# power_supply_module.net
KiCad netlist of a schematic drawn in EAGLE
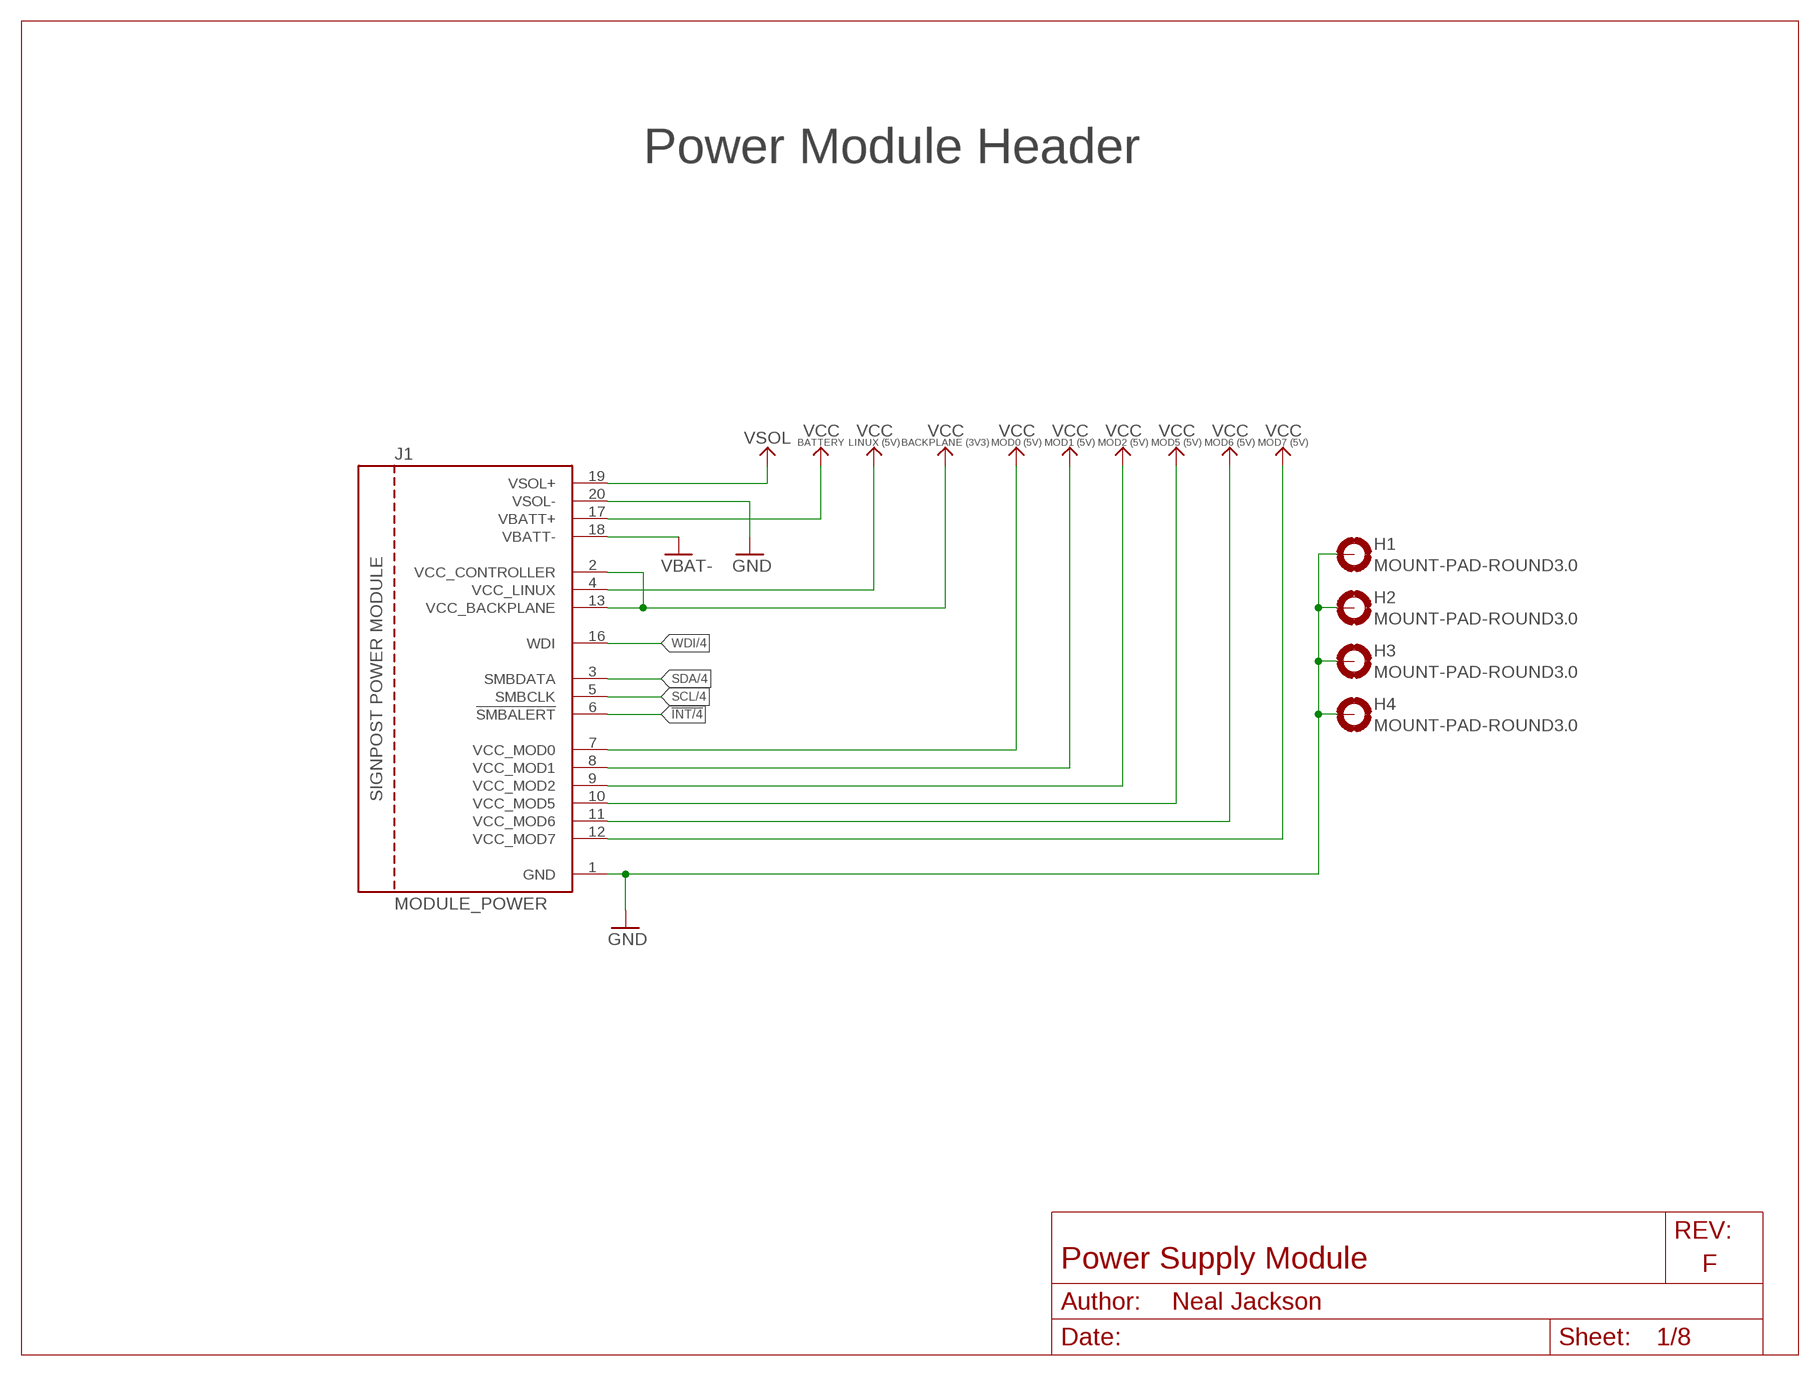
[diagram p0: schematic, sheet 1]
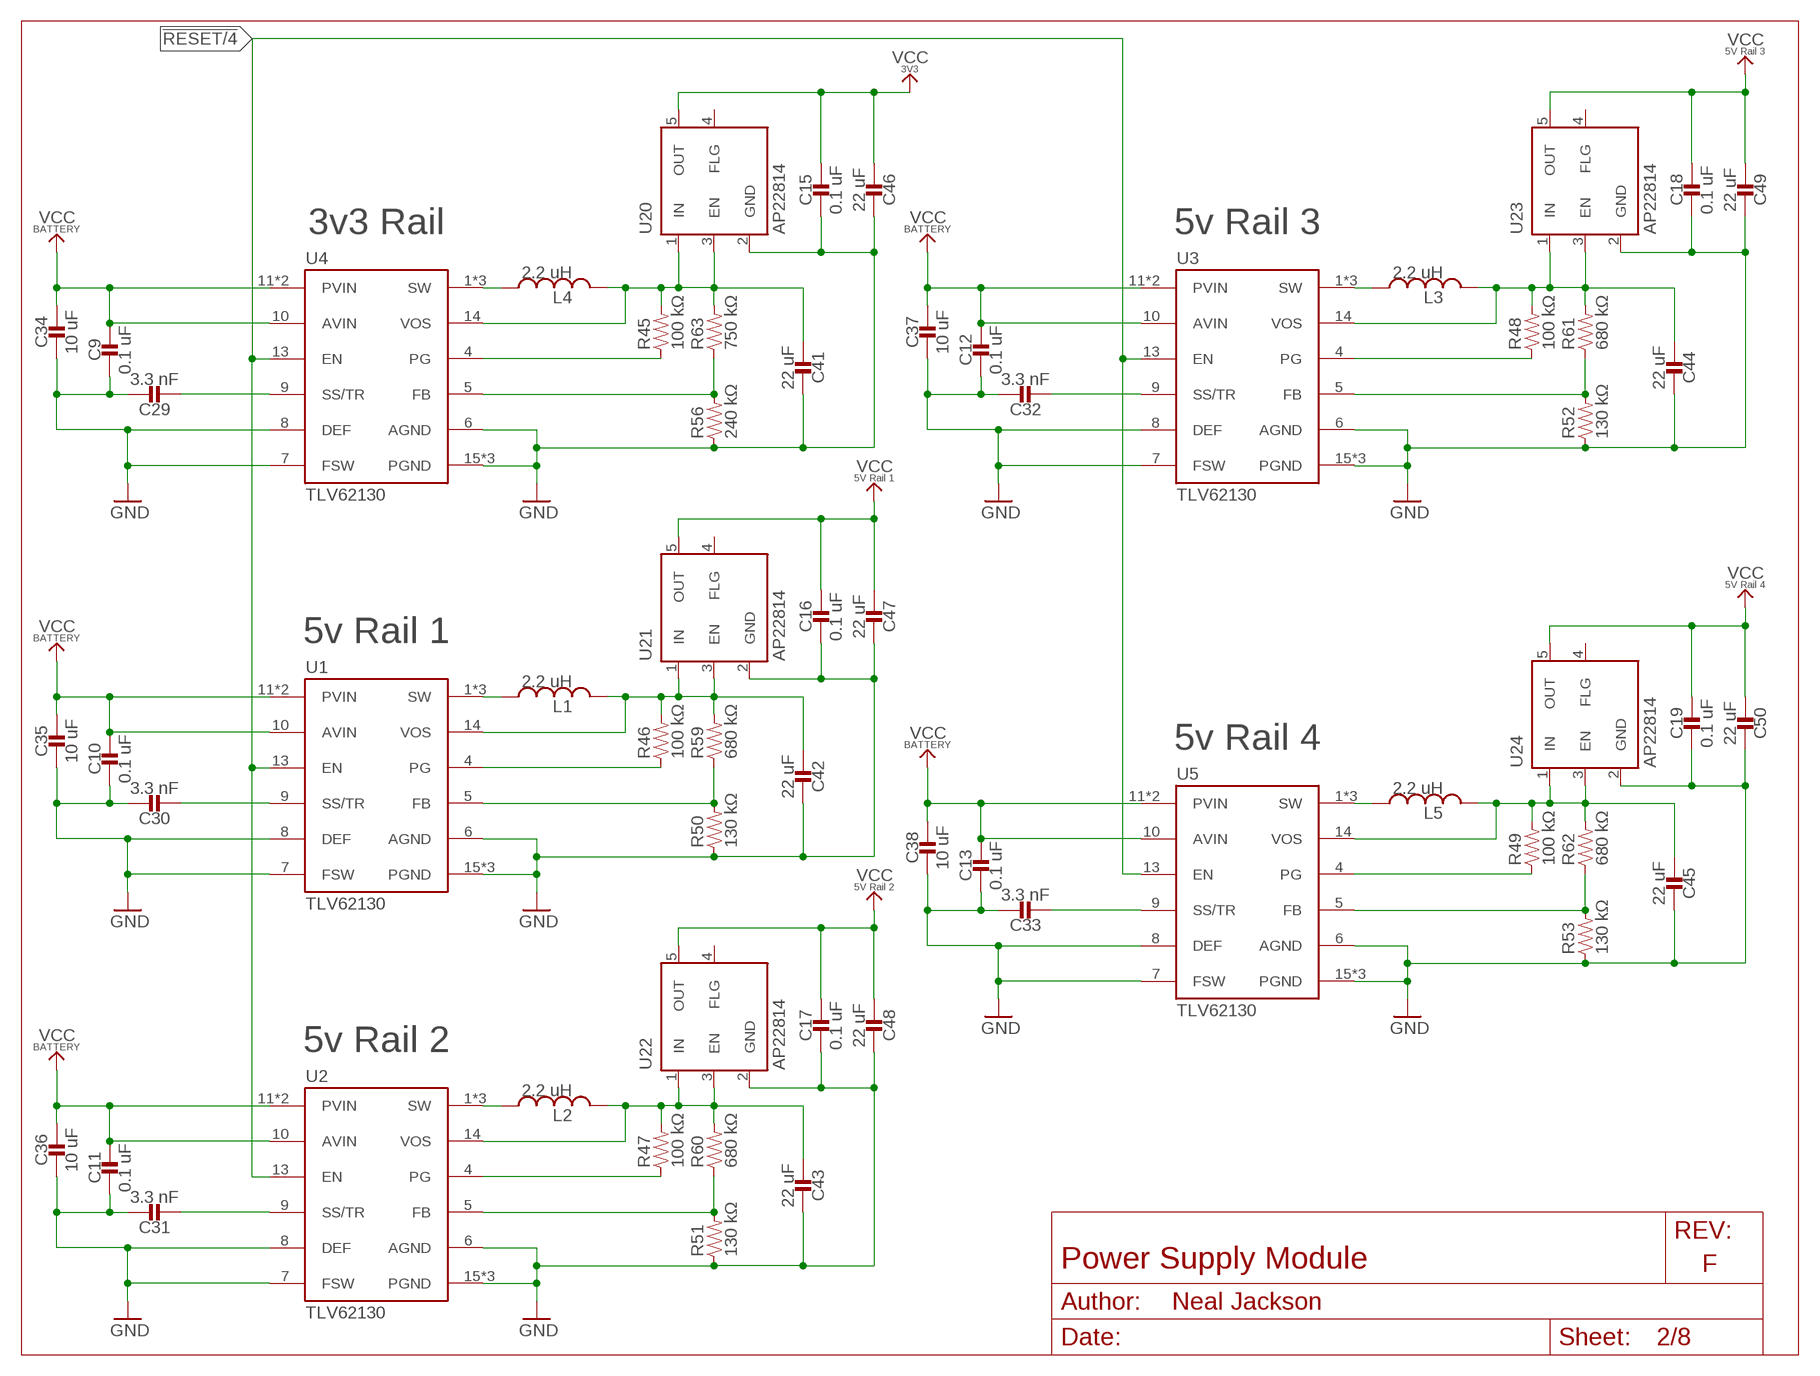
[diagram p1: schematic, sheet 2]
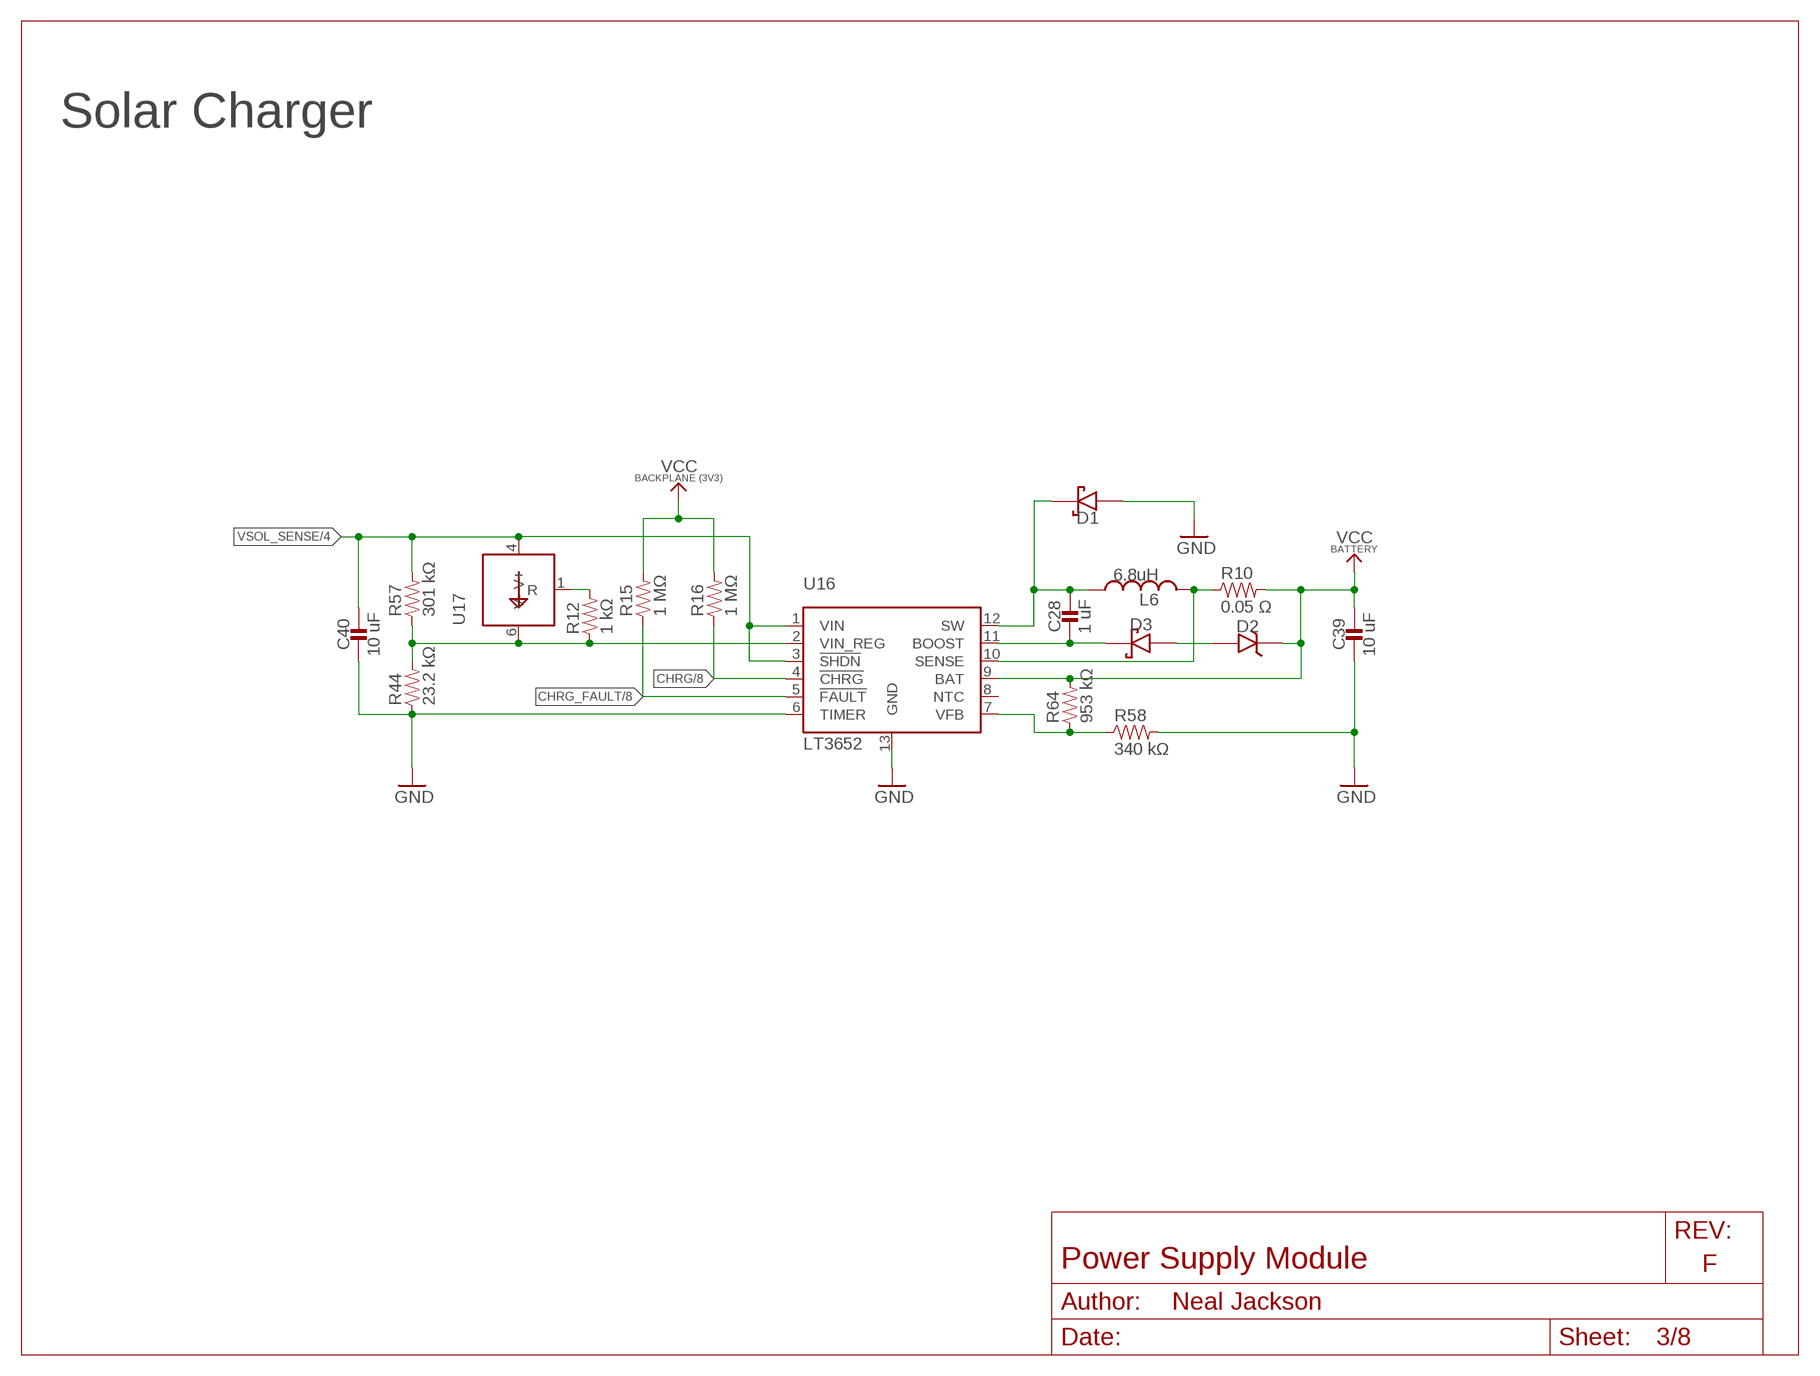
[diagram p2: schematic, sheet 3]
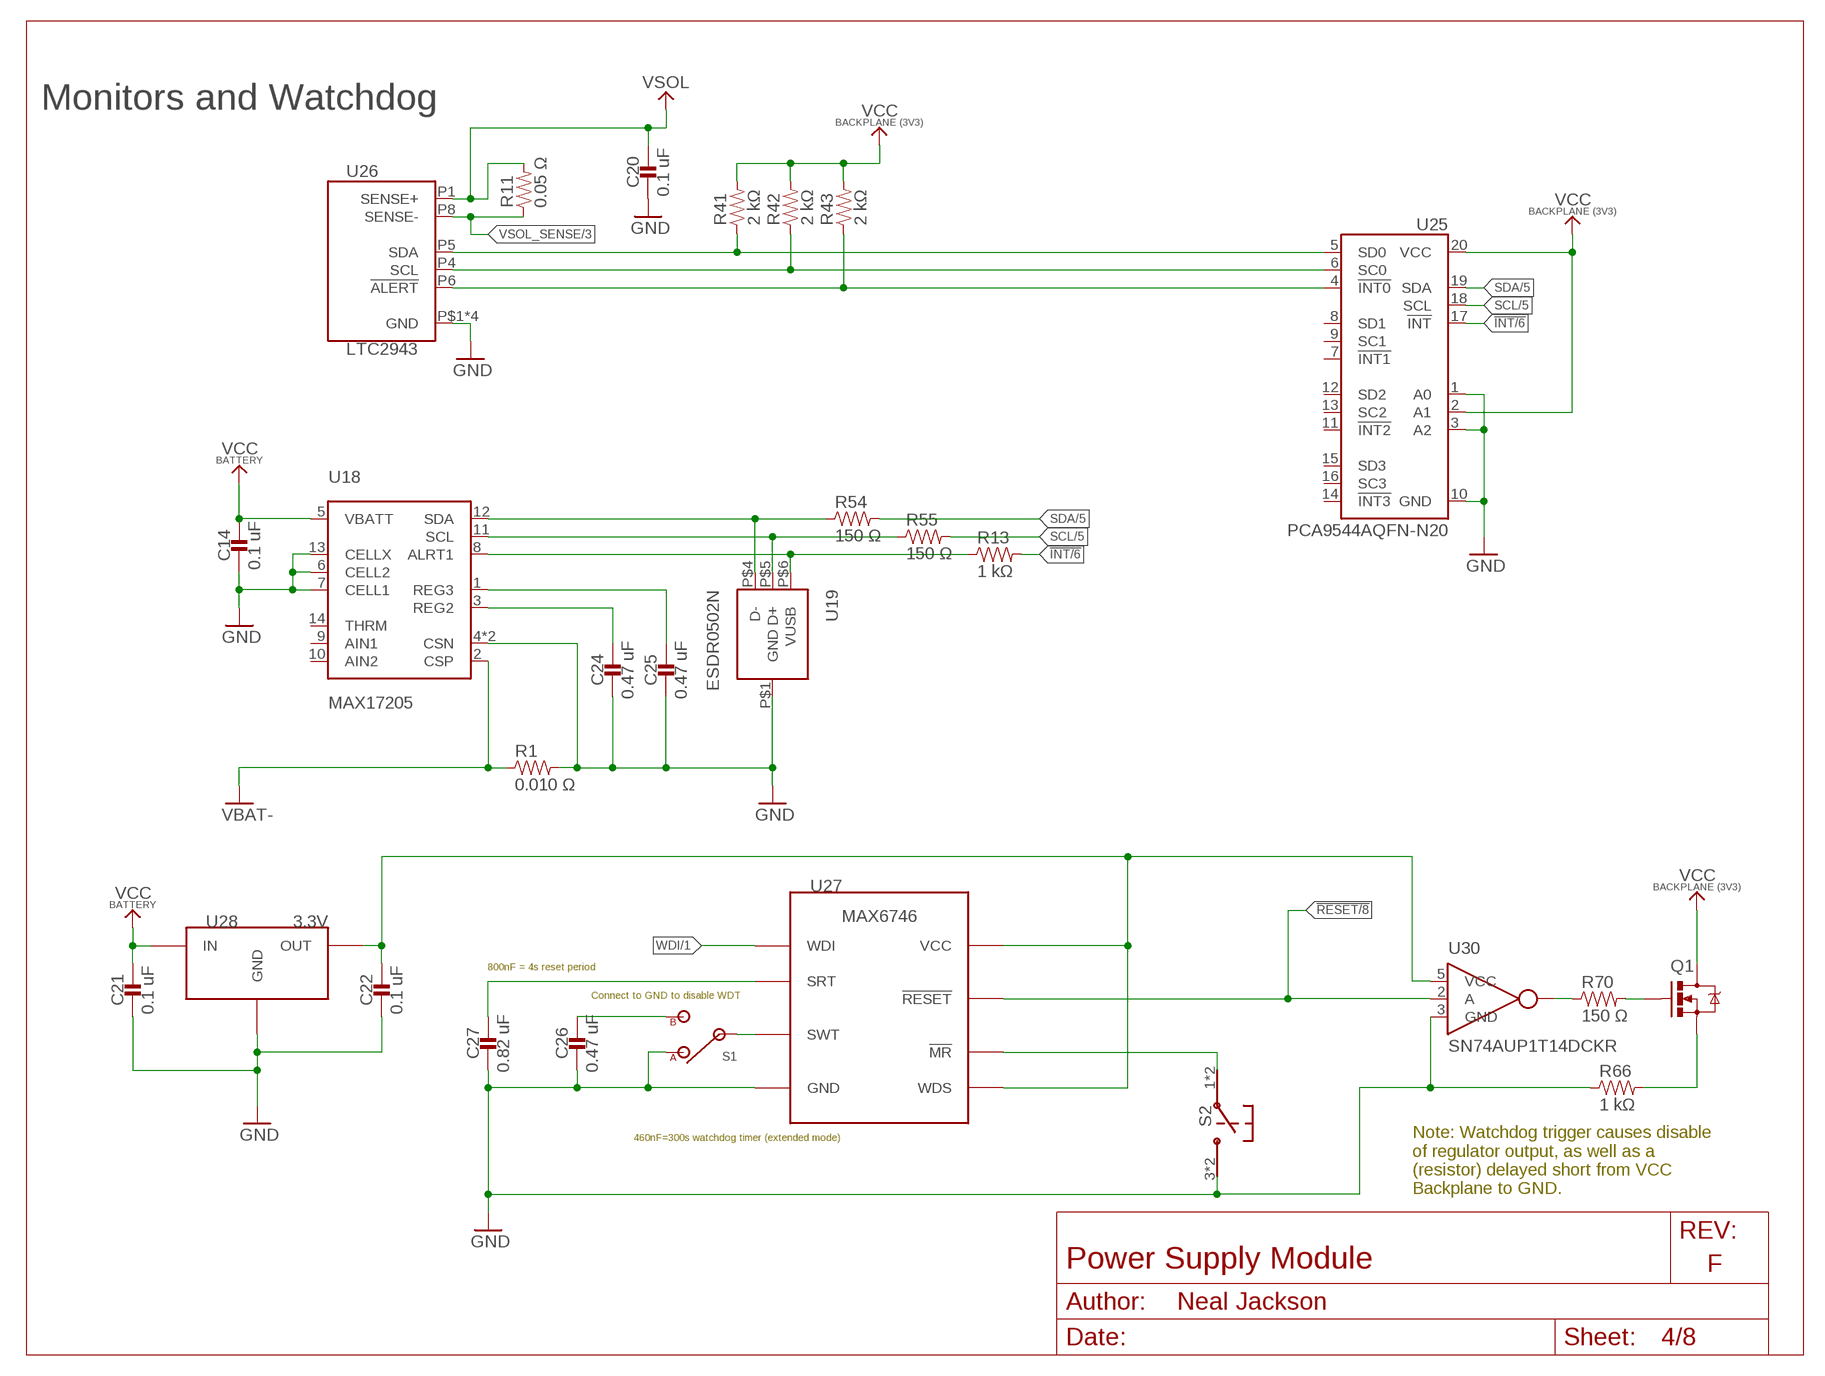
[diagram p3: schematic, sheet 4]
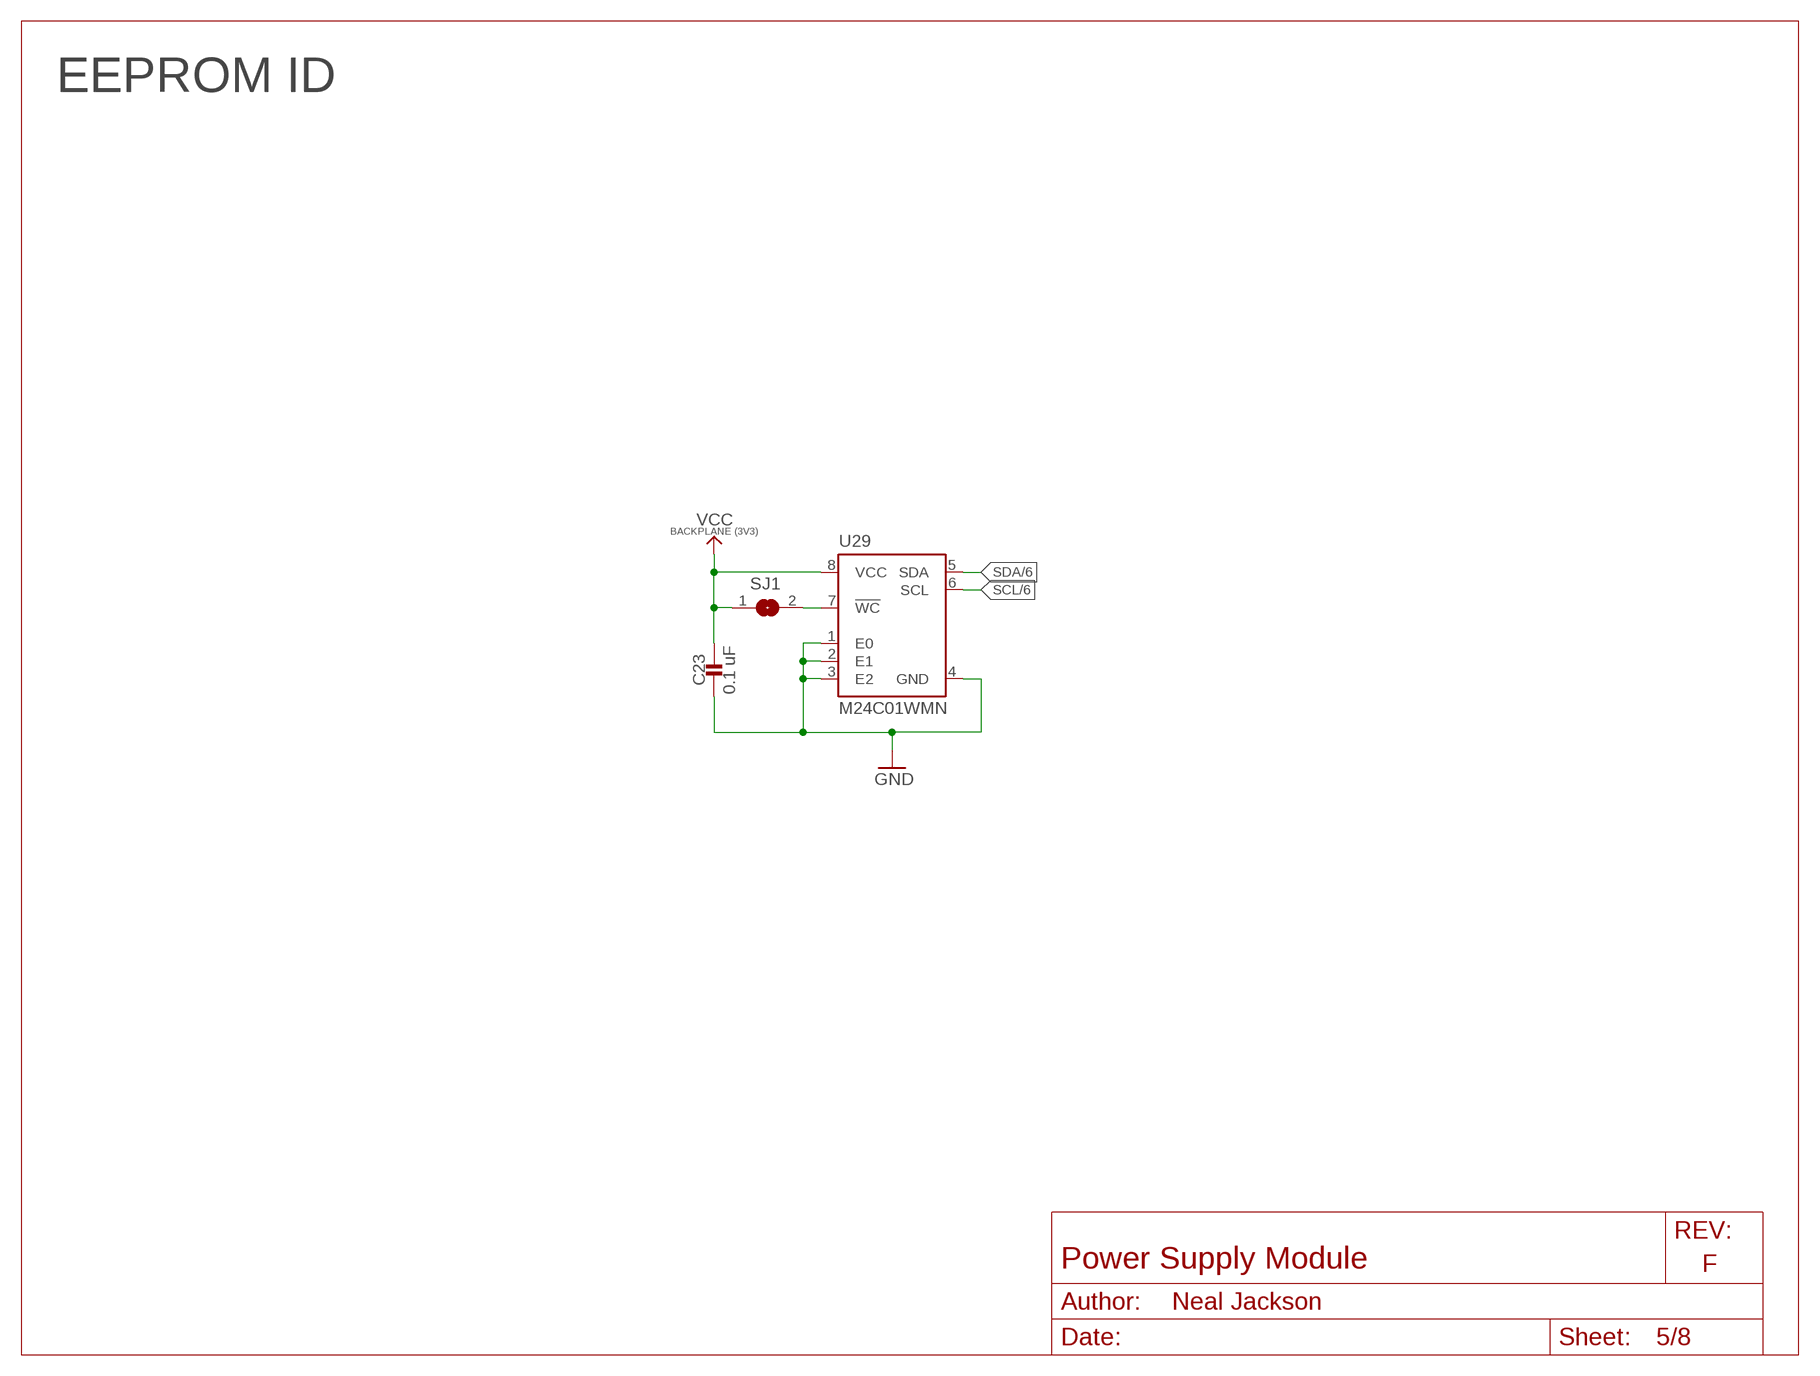
[diagram p4: schematic, sheet 5]
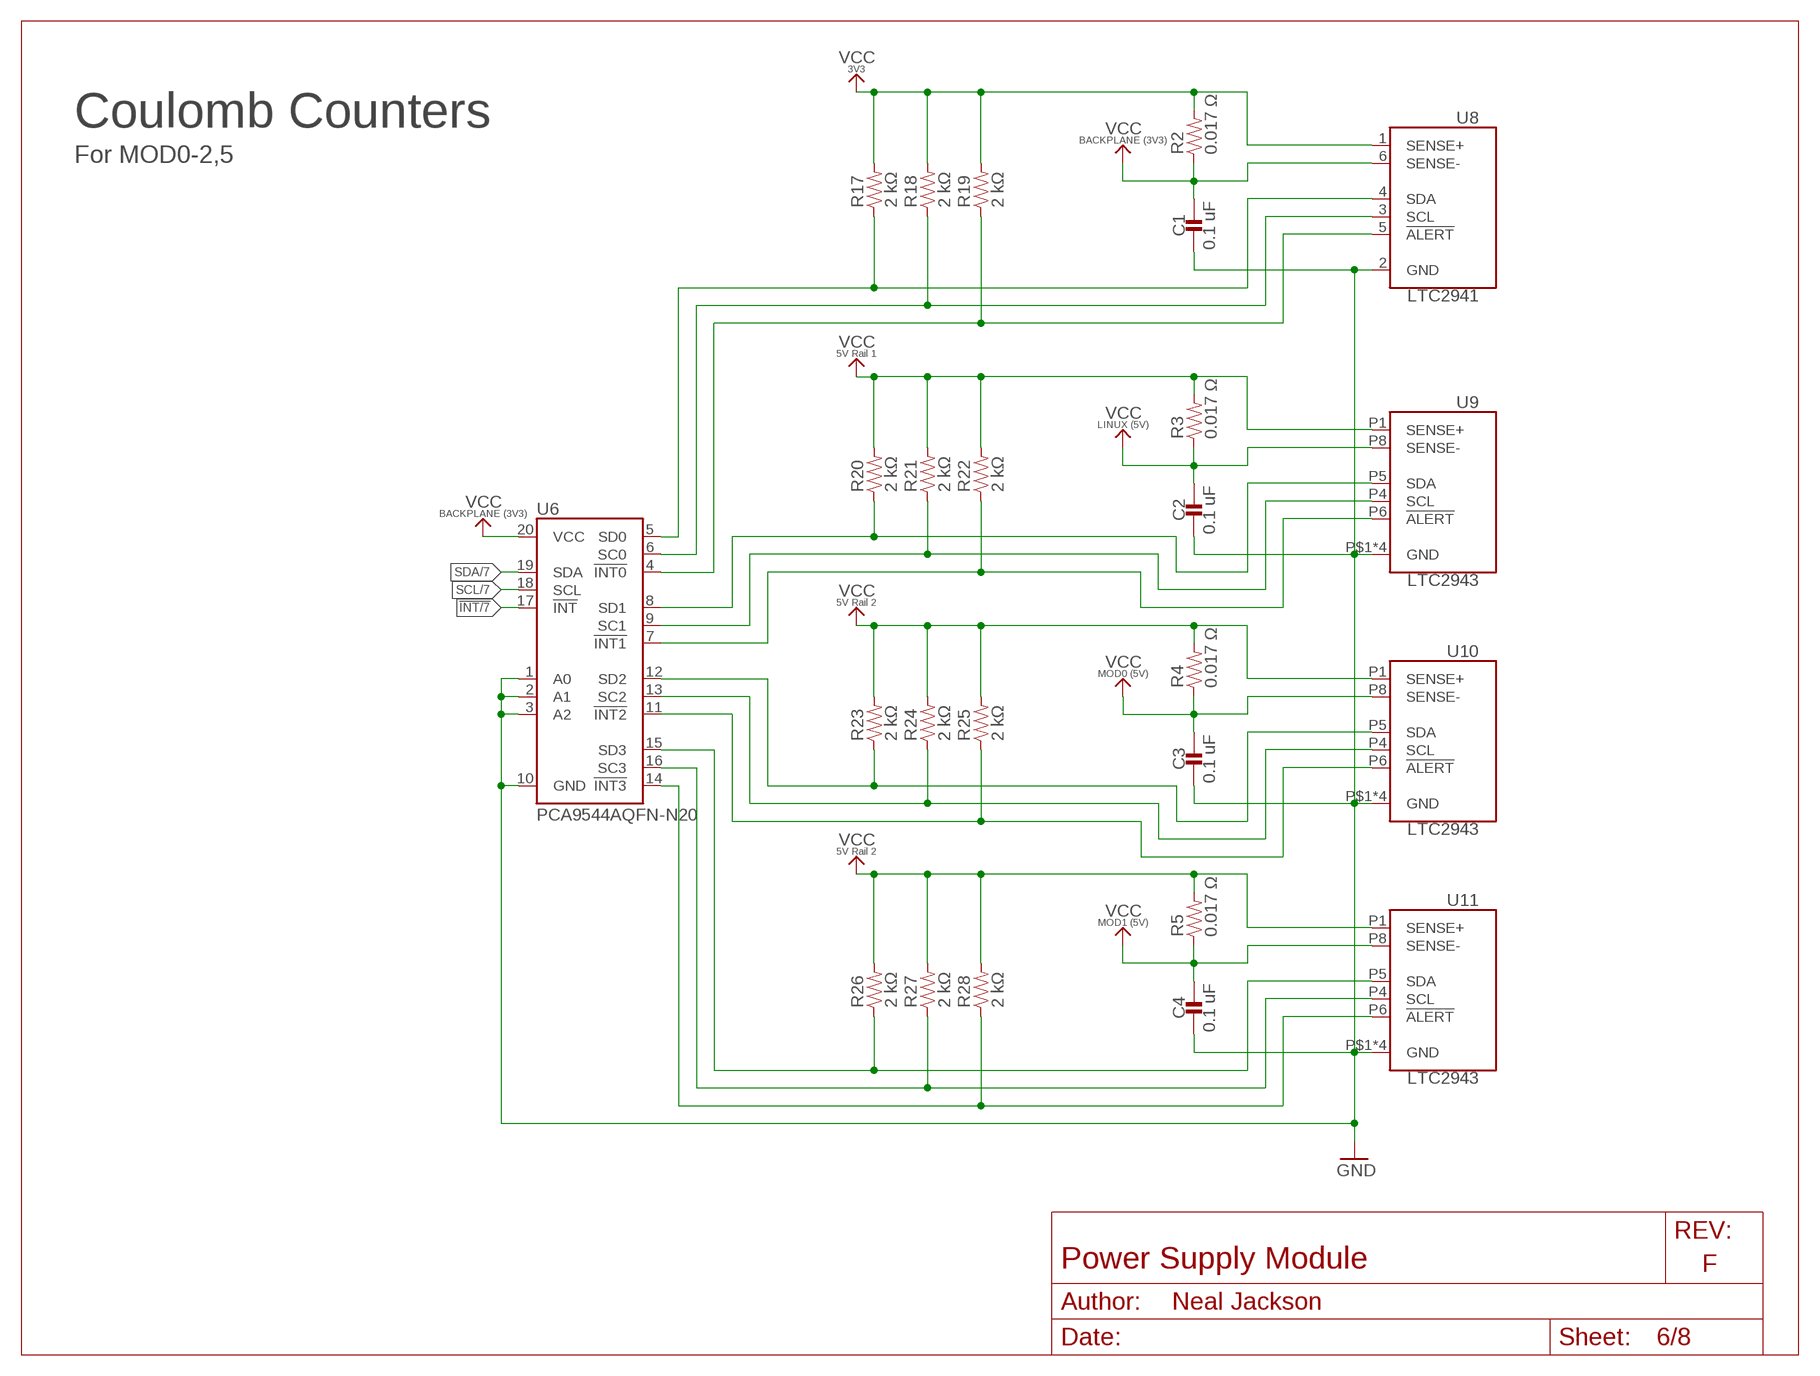
[diagram p5: schematic, sheet 6]
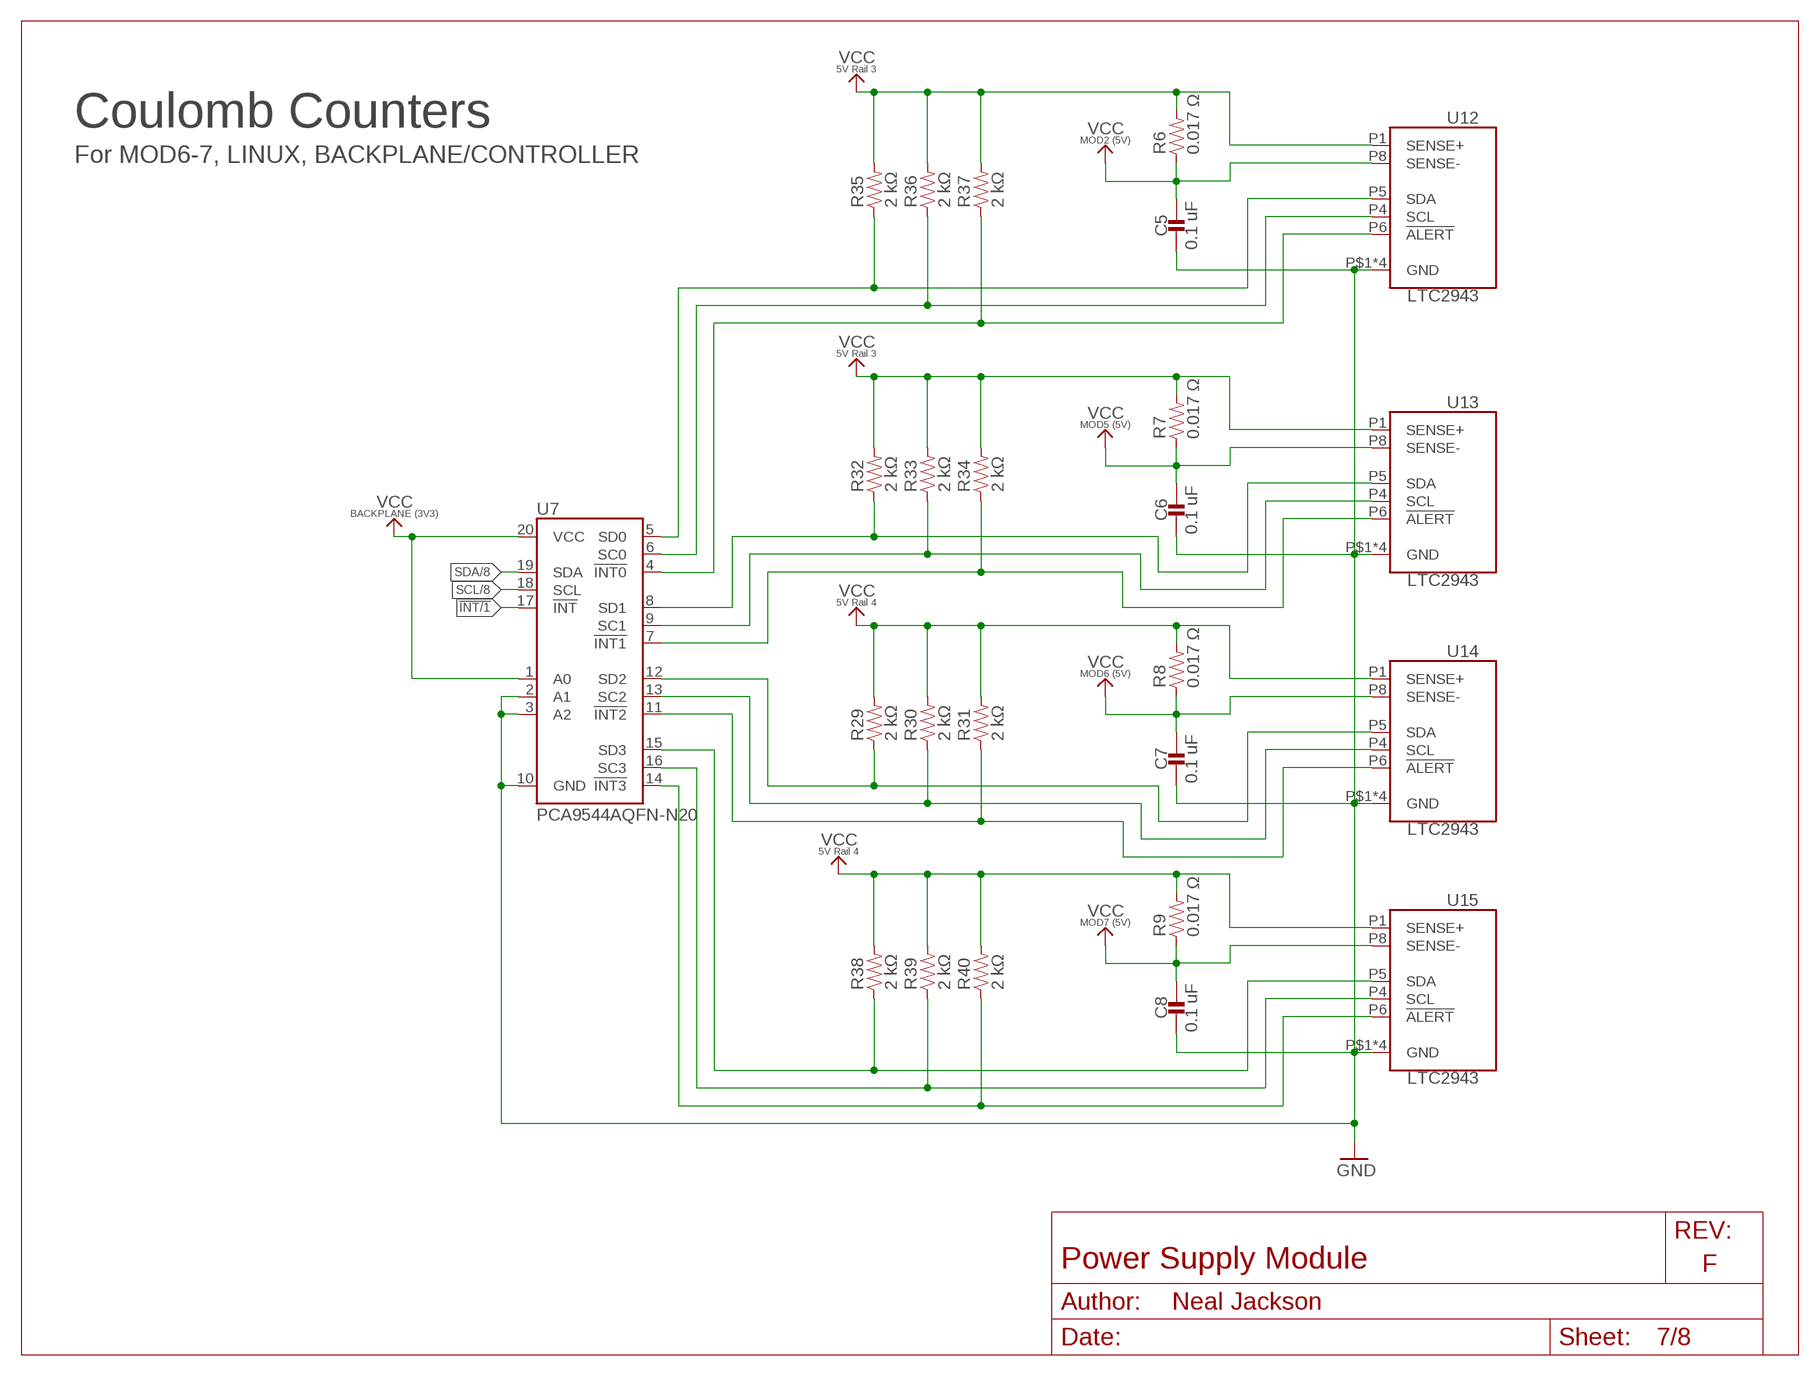
[diagram p6: schematic, sheet 7]
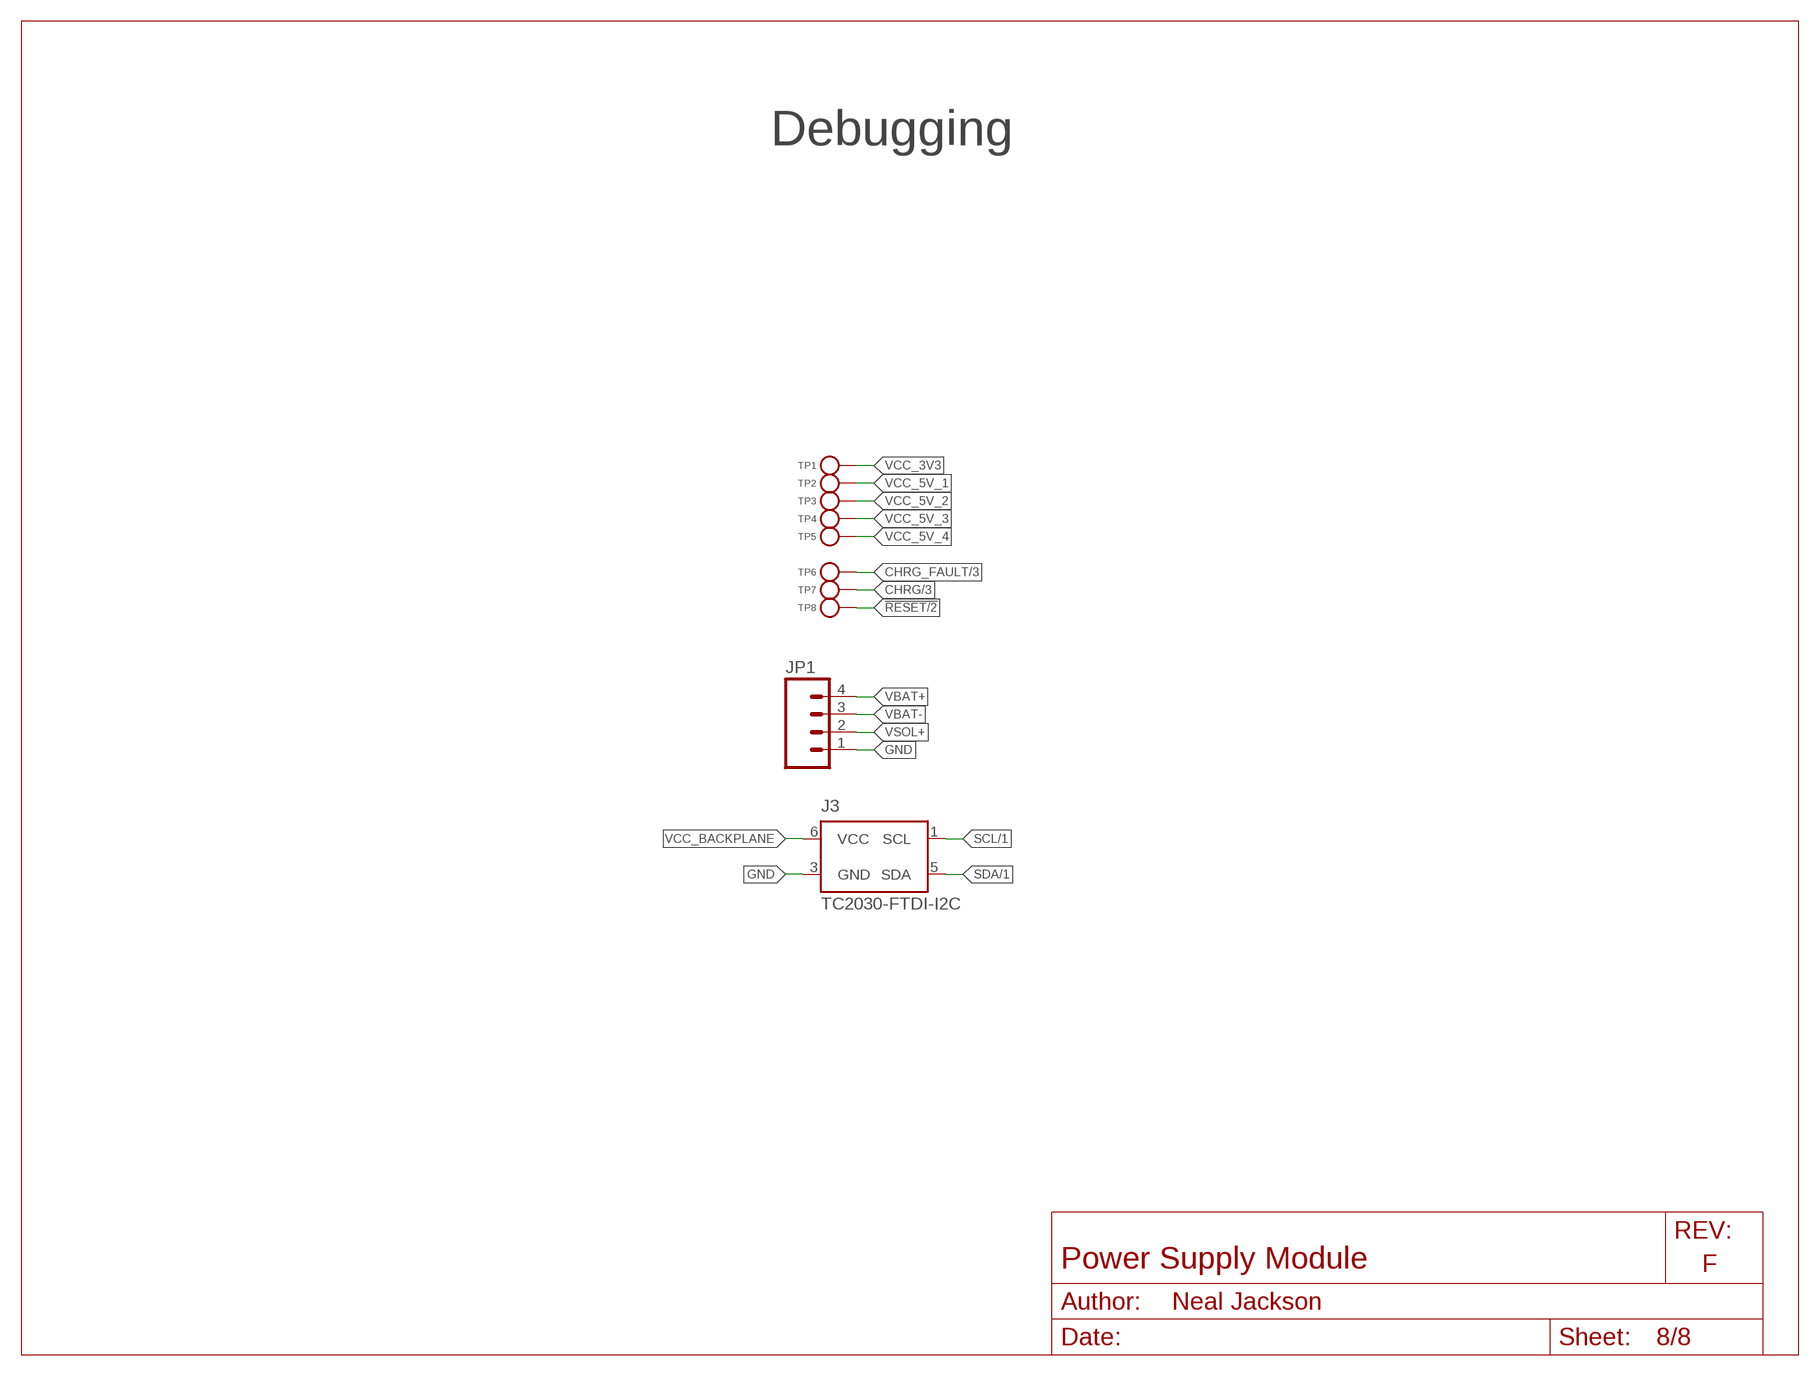
[diagram p7: schematic, sheet 8]

(export (version "E")
  (design (tool "Eeschema 10.0.6"))
  (components
    (comp (ref "C9")
      (value "0.1 uF")
      (footprint "eagle-import:0402_CAP")
      (description "CAP CER 0.1UF 25V X5R 0402")
      (fields (field (name "MANUFACTURER") "Murata") (field (name "MPN") "GRM155R61E104KA87D"))
      (libsource (lib "eagle-import") (part "CAPACITOR0402_CAP"))
    )
    (comp (ref "C10")
      (value "0.1 uF")
      (footprint "eagle-import:0402_CAP")
      (description "CAP CER 0.1UF 25V X5R 0402")
      (fields (field (name "MANUFACTURER") "Murata") (field (name "MPN") "GRM155R61E104KA87D"))
      (libsource (lib "eagle-import") (part "CAPACITOR0402_CAP"))
    )
    (comp (ref "C11")
      (value "0.1 uF")
      (footprint "eagle-import:0402_CAP")
      (description "CAP CER 0.1UF 25V X5R 0402")
      (fields (field (name "MANUFACTURER") "Murata") (field (name "MPN") "GRM155R61E104KA87D"))
      (libsource (lib "eagle-import") (part "CAPACITOR0402_CAP"))
    )
    (comp (ref "C12")
      (value "0.1 uF")
      (footprint "eagle-import:0402_CAP")
      (description "CAP CER 0.1UF 25V X5R 0402")
      (fields (field (name "MANUFACTURER") "Murata") (field (name "MPN") "GRM155R61E104KA87D"))
      (libsource (lib "eagle-import") (part "CAPACITOR0402_CAP"))
    )
    (comp (ref "C13")
      (value "0.1 uF")
      (footprint "eagle-import:0402_CAP")
      (description "CAP CER 0.1UF 25V X5R 0402")
      (fields (field (name "MANUFACTURER") "Murata") (field (name "MPN") "GRM155R61E104KA87D"))
      (libsource (lib "eagle-import") (part "CAPACITOR0402_CAP"))
    )
    (comp (ref "C15")
      (value "0.1 uF")
      (footprint "eagle-import:0402_CAP")
      (description "CAP CER 0.1UF 25V X5R 0402")
      (fields (field (name "MANUFACTURER") "Murata") (field (name "MPN") "GRM155R61E104KA87D"))
      (libsource (lib "eagle-import") (part "CAPACITOR0402_CAP"))
    )
    (comp (ref "C16")
      (value "0.1 uF")
      (footprint "eagle-import:0402_CAP")
      (description "CAP CER 0.1UF 25V X5R 0402")
      (fields (field (name "MANUFACTURER") "Murata") (field (name "MPN") "GRM155R61E104KA87D"))
      (libsource (lib "eagle-import") (part "CAPACITOR0402_CAP"))
    )
    (comp (ref "C17")
      (value "0.1 uF")
      (footprint "eagle-import:0402_CAP")
      (description "CAP CER 0.1UF 25V X5R 0402")
      (fields (field (name "MANUFACTURER") "Murata") (field (name "MPN") "GRM155R61E104KA87D"))
      (libsource (lib "eagle-import") (part "CAPACITOR0402_CAP"))
    )
    (comp (ref "C18")
      (value "0.1 uF")
      (footprint "eagle-import:0402_CAP")
      (description "CAP CER 0.1UF 25V X5R 0402")
      (fields (field (name "MANUFACTURER") "Murata") (field (name "MPN") "GRM155R61E104KA87D"))
      (libsource (lib "eagle-import") (part "CAPACITOR0402_CAP"))
    )
    (comp (ref "C19")
      (value "0.1 uF")
      (footprint "eagle-import:0402_CAP")
      (description "CAP CER 0.1UF 25V X5R 0402")
      (fields (field (name "MANUFACTURER") "Murata") (field (name "MPN") "GRM155R61E104KA87D"))
      (libsource (lib "eagle-import") (part "CAPACITOR0402_CAP"))
    )
    (comp (ref "C29")
      (value "3.3 nF")
      (footprint "eagle-import:0402_CAP")
      (description "CAP CER 3300PF 50V 10% X7R 0402")
      (fields (field (name "MANUFACTURER") "Murata") (field (name "MPN") "GRM155R71H332KA01D"))
      (libsource (lib "eagle-import") (part "CAPACITOR0402_CAP"))
    )
    (comp (ref "C30")
      (value "3.3 nF")
      (footprint "eagle-import:0402_CAP")
      (description "CAP CER 3300PF 50V 10% X7R 0402")
      (fields (field (name "MANUFACTURER") "Murata") (field (name "MPN") "GRM155R71H332KA01D"))
      (libsource (lib "eagle-import") (part "CAPACITOR0402_CAP"))
    )
    (comp (ref "C31")
      (value "3.3 nF")
      (footprint "eagle-import:0402_CAP")
      (description "CAP CER 3300PF 50V 10% X7R 0402")
      (fields (field (name "MANUFACTURER") "Murata") (field (name "MPN") "GRM155R71H332KA01D"))
      (libsource (lib "eagle-import") (part "CAPACITOR0402_CAP"))
    )
    (comp (ref "C32")
      (value "3.3 nF")
      (footprint "eagle-import:0402_CAP")
      (description "CAP CER 3300PF 50V 10% X7R 0402")
      (fields (field (name "MANUFACTURER") "Murata") (field (name "MPN") "GRM155R71H332KA01D"))
      (libsource (lib "eagle-import") (part "CAPACITOR0402_CAP"))
    )
    (comp (ref "C33")
      (value "3.3 nF")
      (footprint "eagle-import:0402_CAP")
      (description "CAP CER 3300PF 50V 10% X7R 0402")
      (fields (field (name "MANUFACTURER") "Murata") (field (name "MPN") "GRM155R71H332KA01D"))
      (libsource (lib "eagle-import") (part "CAPACITOR0402_CAP"))
    )
    (comp (ref "C34")
      (value "10 uF")
      (footprint "eagle-import:0805_CAP")
      (description "CAP CER 10UF 25V 10% X5R 0805")
      (fields (field (name "MANUFACTURER") "Murata") (field (name "MPN") "GRM21BR61E106KA73L"))
      (libsource (lib "eagle-import") (part "CAPACITOR0805_CAP"))
    )
    (comp (ref "C35")
      (value "10 uF")
      (footprint "eagle-import:0805_CAP")
      (description "CAP CER 10UF 25V 10% X5R 0805")
      (fields (field (name "MANUFACTURER") "Murata") (field (name "MPN") "GRM21BR61E106KA73L"))
      (libsource (lib "eagle-import") (part "CAPACITOR0805_CAP"))
    )
    (comp (ref "C36")
      (value "10 uF")
      (footprint "eagle-import:0805_CAP")
      (description "CAP CER 10UF 25V 10% X5R 0805")
      (fields (field (name "MANUFACTURER") "Murata") (field (name "MPN") "GRM21BR61E106KA73L"))
      (libsource (lib "eagle-import") (part "CAPACITOR0805_CAP"))
    )
    (comp (ref "C37")
      (value "10 uF")
      (footprint "eagle-import:0805_CAP")
      (description "CAP CER 10UF 25V 10% X5R 0805")
      (fields (field (name "MANUFACTURER") "Murata") (field (name "MPN") "GRM21BR61E106KA73L"))
      (libsource (lib "eagle-import") (part "CAPACITOR0805_CAP"))
    )
    (comp (ref "C38")
      (value "10 uF")
      (footprint "eagle-import:0805_CAP")
      (description "CAP CER 10UF 25V 10% X5R 0805")
      (fields (field (name "MANUFACTURER") "Murata") (field (name "MPN") "GRM21BR61E106KA73L"))
      (libsource (lib "eagle-import") (part "CAPACITOR0805_CAP"))
    )
    (comp (ref "C41")
      (value "22 uF")
      (footprint "eagle-import:0603_CAP")
      (description "CAP CER 22UF 6.3V X5R 0603")
      (fields (field (name "MANUFACTURER") "Samsung") (field (name "MPN") "CL10A226MQ8NRNC"))
      (libsource (lib "eagle-import") (part "CAPACITOR0603_CAP"))
    )
    (comp (ref "C42")
      (value "22 uF")
      (footprint "eagle-import:0603_CAP")
      (description "CAP CER 22UF 6.3V X5R 0603")
      (fields (field (name "MANUFACTURER") "Samsung") (field (name "MPN") "CL10A226MQ8NRNC"))
      (libsource (lib "eagle-import") (part "CAPACITOR0603_CAP"))
    )
    (comp (ref "C43")
      (value "22 uF")
      (footprint "eagle-import:0603_CAP")
      (description "CAP CER 22UF 6.3V X5R 0603")
      (fields (field (name "MANUFACTURER") "Samsung") (field (name "MPN") "CL10A226MQ8NRNC"))
      (libsource (lib "eagle-import") (part "CAPACITOR0603_CAP"))
    )
    (comp (ref "C44")
      (value "22 uF")
      (footprint "eagle-import:0603_CAP")
      (description "CAP CER 22UF 6.3V X5R 0603")
      (fields (field (name "MANUFACTURER") "Samsung") (field (name "MPN") "CL10A226MQ8NRNC"))
      (libsource (lib "eagle-import") (part "CAPACITOR0603_CAP"))
    )
    (comp (ref "C45")
      (value "22 uF")
      (footprint "eagle-import:0603_CAP")
      (description "CAP CER 22UF 6.3V X5R 0603")
      (fields (field (name "MANUFACTURER") "Samsung") (field (name "MPN") "CL10A226MQ8NRNC"))
      (libsource (lib "eagle-import") (part "CAPACITOR0603_CAP"))
    )
    (comp (ref "C46")
      (value "22 uF")
      (footprint "eagle-import:0603_CAP")
      (description "CAP CER 22UF 6.3V X5R 0603")
      (fields (field (name "MANUFACTURER") "Samsung") (field (name "MPN") "CL10A226MQ8NRNC"))
      (libsource (lib "eagle-import") (part "CAPACITOR0603_CAP"))
    )
    (comp (ref "C47")
      (value "22 uF")
      (footprint "eagle-import:0603_CAP")
      (description "CAP CER 22UF 6.3V X5R 0603")
      (fields (field (name "MANUFACTURER") "Samsung") (field (name "MPN") "CL10A226MQ8NRNC"))
      (libsource (lib "eagle-import") (part "CAPACITOR0603_CAP"))
    )
    (comp (ref "C48")
      (value "22 uF")
      (footprint "eagle-import:0603_CAP")
      (description "CAP CER 22UF 6.3V X5R 0603")
      (fields (field (name "MANUFACTURER") "Samsung") (field (name "MPN") "CL10A226MQ8NRNC"))
      (libsource (lib "eagle-import") (part "CAPACITOR0603_CAP"))
    )
    (comp (ref "C49")
      (value "22 uF")
      (footprint "eagle-import:0603_CAP")
      (description "CAP CER 22UF 6.3V X5R 0603")
      (fields (field (name "MANUFACTURER") "Samsung") (field (name "MPN") "CL10A226MQ8NRNC"))
      (libsource (lib "eagle-import") (part "CAPACITOR0603_CAP"))
    )
    (comp (ref "C50")
      (value "22 uF")
      (footprint "eagle-import:0603_CAP")
      (description "CAP CER 22UF 6.3V X5R 0603")
      (fields (field (name "MANUFACTURER") "Samsung") (field (name "MPN") "CL10A226MQ8NRNC"))
      (libsource (lib "eagle-import") (part "CAPACITOR0603_CAP"))
    )
    (comp (ref "L1")
      (value "2.2 uH")
      (footprint "eagle-import:IHL-1212BZ-11")
      (fields (field (name "MANUFACTURER") "Vishay Dale") (field (name "MPN") "IHLP1212BZER2R2M11"))
      (libsource (lib "eagle-import") (part "INDUCTORIHL"))
    )
    (comp (ref "L2")
      (value "2.2 uH")
      (footprint "eagle-import:IHL-1212BZ-11")
      (fields (field (name "MANUFACTURER") "Vishay Dale") (field (name "MPN") "IHLP1212BZER2R2M11"))
      (libsource (lib "eagle-import") (part "INDUCTORIHL"))
    )
    (comp (ref "L3")
      (value "2.2 uH")
      (footprint "eagle-import:IHL-1212BZ-11")
      (fields (field (name "MANUFACTURER") "Vishay Dale") (field (name "MPN") "IHLP1212BZER2R2M11"))
      (libsource (lib "eagle-import") (part "INDUCTORIHL"))
    )
    (comp (ref "L4")
      (value "2.2 uH")
      (footprint "eagle-import:IHL-1212BZ-11")
      (fields (field (name "MANUFACTURER") "Vishay Dale") (field (name "MPN") "IHLP1212BZER2R2M11"))
      (libsource (lib "eagle-import") (part "INDUCTORIHL"))
    )
    (comp (ref "L5")
      (value "2.2 uH")
      (footprint "eagle-import:IHL-1212BZ-11")
      (fields (field (name "MANUFACTURER") "Vishay Dale") (field (name "MPN") "IHLP1212BZER2R2M11"))
      (libsource (lib "eagle-import") (part "INDUCTORIHL"))
    )
    (comp (ref "R45")
      (value "100 kΩ")
      (footprint "eagle-import:0402_RES")
      (description "RES SMD 100K OHM 5% 1/10W 0402")
      (fields (field (name "MANUFACTURER") "Panasonic") (field (name "MPN") "ERJ-2GEJ104X"))
      (libsource (lib "eagle-import") (part "RESISTOR0402_RES"))
    )
    (comp (ref "R46")
      (value "100 kΩ")
      (footprint "eagle-import:0402_RES")
      (description "RES SMD 100K OHM 5% 1/10W 0402")
      (fields (field (name "MANUFACTURER") "Panasonic") (field (name "MPN") "ERJ-2GEJ104X"))
      (libsource (lib "eagle-import") (part "RESISTOR0402_RES"))
    )
    (comp (ref "R47")
      (value "100 kΩ")
      (footprint "eagle-import:0402_RES")
      (description "RES SMD 100K OHM 5% 1/10W 0402")
      (fields (field (name "MANUFACTURER") "Panasonic") (field (name "MPN") "ERJ-2GEJ104X"))
      (libsource (lib "eagle-import") (part "RESISTOR0402_RES"))
    )
    (comp (ref "R48")
      (value "100 kΩ")
      (footprint "eagle-import:0402_RES")
      (description "RES SMD 100K OHM 5% 1/10W 0402")
      (fields (field (name "MANUFACTURER") "Panasonic") (field (name "MPN") "ERJ-2GEJ104X"))
      (libsource (lib "eagle-import") (part "RESISTOR0402_RES"))
    )
    (comp (ref "R49")
      (value "100 kΩ")
      (footprint "eagle-import:0402_RES")
      (description "RES SMD 100K OHM 5% 1/10W 0402")
      (fields (field (name "MANUFACTURER") "Panasonic") (field (name "MPN") "ERJ-2GEJ104X"))
      (libsource (lib "eagle-import") (part "RESISTOR0402_RES"))
    )
    (comp (ref "R50")
      (value "130 kΩ")
      (footprint "eagle-import:0402_RES")
      (description "RES SMD 130K OHM 1% 1/10W 0402")
      (fields (field (name "MANUFACTURER") "Panasonic") (field (name "MPN") "ERJ-2RKF1303X"))
      (libsource (lib "eagle-import") (part "RESISTOR0402_RES"))
    )
    (comp (ref "R51")
      (value "130 kΩ")
      (footprint "eagle-import:0402_RES")
      (description "RES SMD 130K OHM 1% 1/10W 0402")
      (fields (field (name "MANUFACTURER") "Panasonic") (field (name "MPN") "ERJ-2RKF1303X"))
      (libsource (lib "eagle-import") (part "RESISTOR0402_RES"))
    )
    (comp (ref "R52")
      (value "130 kΩ")
      (footprint "eagle-import:0402_RES")
      (description "RES SMD 130K OHM 1% 1/10W 0402")
      (fields (field (name "MANUFACTURER") "Panasonic") (field (name "MPN") "ERJ-2RKF1303X"))
      (libsource (lib "eagle-import") (part "RESISTOR0402_RES"))
    )
    (comp (ref "R53")
      (value "130 kΩ")
      (footprint "eagle-import:0402_RES")
      (description "RES SMD 130K OHM 1% 1/10W 0402")
      (fields (field (name "MANUFACTURER") "Panasonic") (field (name "MPN") "ERJ-2RKF1303X"))
      (libsource (lib "eagle-import") (part "RESISTOR0402_RES"))
    )
    (comp (ref "R56")
      (value "240 kΩ")
      (footprint "eagle-import:0402_RES")
      (description "RES SMD 240K OHM 1% 1/10W 0402")
      (fields (field (name "MANUFACTURER") "Panasonic") (field (name "MPN") "ERJ-2RKF2403X"))
      (libsource (lib "eagle-import") (part "RESISTOR0402_RES"))
    )
    (comp (ref "R59")
      (value "680 kΩ")
      (footprint "eagle-import:0402_RES")
      (description "RES SMD 680K OHM 1% 1/10W 0402")
      (fields (field (name "MANUFACTURER") "Panasonic") (field (name "MPN") "ERJ-2RKF6803X"))
      (libsource (lib "eagle-import") (part "RESISTOR0402_RES"))
    )
    (comp (ref "R60")
      (value "680 kΩ")
      (footprint "eagle-import:0402_RES")
      (description "RES SMD 680K OHM 1% 1/10W 0402")
      (fields (field (name "MANUFACTURER") "Panasonic") (field (name "MPN") "ERJ-2RKF6803X"))
      (libsource (lib "eagle-import") (part "RESISTOR0402_RES"))
    )
    (comp (ref "R61")
      (value "680 kΩ")
      (footprint "eagle-import:0402_RES")
      (description "RES SMD 680K OHM 1% 1/10W 0402")
      (fields (field (name "MANUFACTURER") "Panasonic") (field (name "MPN") "ERJ-2RKF6803X"))
      (libsource (lib "eagle-import") (part "RESISTOR0402_RES"))
    )
    (comp (ref "R62")
      (value "680 kΩ")
      (footprint "eagle-import:0402_RES")
      (description "RES SMD 680K OHM 1% 1/10W 0402")
      (fields (field (name "MANUFACTURER") "Panasonic") (field (name "MPN") "ERJ-2RKF6803X"))
      (libsource (lib "eagle-import") (part "RESISTOR0402_RES"))
    )
    (comp (ref "R63")
      (value "750 kΩ")
      (footprint "eagle-import:0402_RES")
      (description "RES SMD 750K OHM 5% 1/10W 0402")
      (fields (field (name "MANUFACTURER") "Panasonic") (field (name "MPN") "ERJ-2GEJ754X"))
      (libsource (lib "eagle-import") (part "RESISTOR0402_RES"))
    )
    (comp (ref "U1")
      (value "TLV62130")
      (footprint "eagle-import:TQFN-16_3MM")
      (fields (field (name "MANUFACTURER") "Texas Instruments") (field (name "MPN") "TLV62130RGTR"))
      (libsource (lib "eagle-import") (part "TLV62130"))
    )
    (comp (ref "U2")
      (value "TLV62130")
      (footprint "eagle-import:TQFN-16_3MM")
      (fields (field (name "MANUFACTURER") "Texas Instruments") (field (name "MPN") "TLV62130RGTR"))
      (libsource (lib "eagle-import") (part "TLV62130"))
    )
    (comp (ref "U3")
      (value "TLV62130")
      (footprint "eagle-import:TQFN-16_3MM")
      (fields (field (name "MANUFACTURER") "Texas Instruments") (field (name "MPN") "TLV62130RGTR"))
      (libsource (lib "eagle-import") (part "TLV62130"))
    )
    (comp (ref "U4")
      (value "TLV62130")
      (footprint "eagle-import:TQFN-16_3MM")
      (fields (field (name "MANUFACTURER") "Texas Instruments") (field (name "MPN") "TLV62130RGTR"))
      (libsource (lib "eagle-import") (part "TLV62130"))
    )
    (comp (ref "U5")
      (value "TLV62130")
      (footprint "eagle-import:TQFN-16_3MM")
      (fields (field (name "MANUFACTURER") "Texas Instruments") (field (name "MPN") "TLV62130RGTR"))
      (libsource (lib "eagle-import") (part "TLV62130"))
    )
    (comp (ref "U20")
      (value "AP22814")
      (footprint "eagle-import:U-DFN2020-6")
      (libsource (lib "eagle-import") (part "AP22814"))
    )
    (comp (ref "U21")
      (value "AP22814")
      (footprint "eagle-import:U-DFN2020-6")
      (libsource (lib "eagle-import") (part "AP22814"))
    )
    (comp (ref "U22")
      (value "AP22814")
      (footprint "eagle-import:U-DFN2020-6")
      (libsource (lib "eagle-import") (part "AP22814"))
    )
    (comp (ref "U23")
      (value "AP22814")
      (footprint "eagle-import:U-DFN2020-6")
      (libsource (lib "eagle-import") (part "AP22814"))
    )
    (comp (ref "U24")
      (value "AP22814")
      (footprint "eagle-import:U-DFN2020-6")
      (libsource (lib "eagle-import") (part "AP22814"))
    )
    (comp (ref "C1")
      (value "0.1 uF")
      (footprint "eagle-import:0402_CAP")
      (description "CAP CER 0.1UF 25V X5R 0402")
      (fields (field (name "MANUFACTURER") "Murata") (field (name "MPN") "GRM155R61E104KA87D"))
      (libsource (lib "eagle-import") (part "CAPACITOR0402_CAP"))
    )
    (comp (ref "C2")
      (value "0.1 uF")
      (footprint "eagle-import:0402_CAP")
      (description "CAP CER 0.1UF 25V X5R 0402")
      (fields (field (name "MANUFACTURER") "Murata") (field (name "MPN") "GRM155R61E104KA87D"))
      (libsource (lib "eagle-import") (part "CAPACITOR0402_CAP"))
    )
    (comp (ref "C3")
      (value "0.1 uF")
      (footprint "eagle-import:0402_CAP")
      (description "CAP CER 0.1UF 25V X5R 0402")
      (fields (field (name "MANUFACTURER") "Murata") (field (name "MPN") "GRM155R61E104KA87D"))
      (libsource (lib "eagle-import") (part "CAPACITOR0402_CAP"))
    )
    (comp (ref "C4")
      (value "0.1 uF")
      (footprint "eagle-import:0402_CAP")
      (description "CAP CER 0.1UF 25V X5R 0402")
      (fields (field (name "MANUFACTURER") "Murata") (field (name "MPN") "GRM155R61E104KA87D"))
      (libsource (lib "eagle-import") (part "CAPACITOR0402_CAP"))
    )
    (comp (ref "R2")
      (value "0.017 Ω")
      (footprint "eagle-import:0805_RES")
      (description "RES SMD 0.017 OHM 1% 1/2W 0805")
      (fields (field (name "MANUFACTURER") "Vishay Dale") (field (name "MPN") "WSLP0805R0170FEB"))
      (libsource (lib "eagle-import") (part "RESISTOR0805_RES"))
    )
    (comp (ref "R3")
      (value "0.017 Ω")
      (footprint "eagle-import:0805_RES")
      (description "RES SMD 0.017 OHM 1% 1/2W 0805")
      (fields (field (name "MANUFACTURER") "Vishay Dale") (field (name "MPN") "WSLP0805R0170FEB"))
      (libsource (lib "eagle-import") (part "RESISTOR0805_RES"))
    )
    (comp (ref "R4")
      (value "0.017 Ω")
      (footprint "eagle-import:0805_RES")
      (description "RES SMD 0.017 OHM 1% 1/2W 0805")
      (fields (field (name "MANUFACTURER") "Vishay Dale") (field (name "MPN") "WSLP0805R0170FEB"))
      (libsource (lib "eagle-import") (part "RESISTOR0805_RES"))
    )
    (comp (ref "R5")
      (value "0.017 Ω")
      (footprint "eagle-import:0805_RES")
      (description "RES SMD 0.017 OHM 1% 1/2W 0805")
      (fields (field (name "MANUFACTURER") "Vishay Dale") (field (name "MPN") "WSLP0805R0170FEB"))
      (libsource (lib "eagle-import") (part "RESISTOR0805_RES"))
    )
    (comp (ref "R17")
      (value "2 kΩ")
      (footprint "eagle-import:0402_RES")
      (description "RES SMD 2K OHM 1% 1/10W 0402")
      (fields (field (name "MANUFACTURER") "Panasonic") (field (name "MPN") "ERJ-2RKF2001X"))
      (libsource (lib "eagle-import") (part "RESISTOR0402_RES"))
    )
    (comp (ref "R18")
      (value "2 kΩ")
      (footprint "eagle-import:0402_RES")
      (description "RES SMD 2K OHM 1% 1/10W 0402")
      (fields (field (name "MANUFACTURER") "Panasonic") (field (name "MPN") "ERJ-2RKF2001X"))
      (libsource (lib "eagle-import") (part "RESISTOR0402_RES"))
    )
    (comp (ref "R19")
      (value "2 kΩ")
      (footprint "eagle-import:0402_RES")
      (description "RES SMD 2K OHM 1% 1/10W 0402")
      (fields (field (name "MANUFACTURER") "Panasonic") (field (name "MPN") "ERJ-2RKF2001X"))
      (libsource (lib "eagle-import") (part "RESISTOR0402_RES"))
    )
    (comp (ref "R20")
      (value "2 kΩ")
      (footprint "eagle-import:0402_RES")
      (description "RES SMD 2K OHM 1% 1/10W 0402")
      (fields (field (name "MANUFACTURER") "Panasonic") (field (name "MPN") "ERJ-2RKF2001X"))
      (libsource (lib "eagle-import") (part "RESISTOR0402_RES"))
    )
    (comp (ref "R21")
      (value "2 kΩ")
      (footprint "eagle-import:0402_RES")
      (description "RES SMD 2K OHM 1% 1/10W 0402")
      (fields (field (name "MANUFACTURER") "Panasonic") (field (name "MPN") "ERJ-2RKF2001X"))
      (libsource (lib "eagle-import") (part "RESISTOR0402_RES"))
    )
    (comp (ref "R22")
      (value "2 kΩ")
      (footprint "eagle-import:0402_RES")
      (description "RES SMD 2K OHM 1% 1/10W 0402")
      (fields (field (name "MANUFACTURER") "Panasonic") (field (name "MPN") "ERJ-2RKF2001X"))
      (libsource (lib "eagle-import") (part "RESISTOR0402_RES"))
    )
    (comp (ref "R23")
      (value "2 kΩ")
      (footprint "eagle-import:0402_RES")
      (description "RES SMD 2K OHM 1% 1/10W 0402")
      (fields (field (name "MANUFACTURER") "Panasonic") (field (name "MPN") "ERJ-2RKF2001X"))
      (libsource (lib "eagle-import") (part "RESISTOR0402_RES"))
    )
    (comp (ref "R24")
      (value "2 kΩ")
      (footprint "eagle-import:0402_RES")
      (description "RES SMD 2K OHM 1% 1/10W 0402")
      (fields (field (name "MANUFACTURER") "Panasonic") (field (name "MPN") "ERJ-2RKF2001X"))
      (libsource (lib "eagle-import") (part "RESISTOR0402_RES"))
    )
    (comp (ref "R25")
      (value "2 kΩ")
      (footprint "eagle-import:0402_RES")
      (description "RES SMD 2K OHM 1% 1/10W 0402")
      (fields (field (name "MANUFACTURER") "Panasonic") (field (name "MPN") "ERJ-2RKF2001X"))
      (libsource (lib "eagle-import") (part "RESISTOR0402_RES"))
    )
    (comp (ref "R26")
      (value "2 kΩ")
      (footprint "eagle-import:0402_RES")
      (description "RES SMD 2K OHM 1% 1/10W 0402")
      (fields (field (name "MANUFACTURER") "Panasonic") (field (name "MPN") "ERJ-2RKF2001X"))
      (libsource (lib "eagle-import") (part "RESISTOR0402_RES"))
    )
    (comp (ref "R27")
      (value "2 kΩ")
      (footprint "eagle-import:0402_RES")
      (description "RES SMD 2K OHM 1% 1/10W 0402")
      (fields (field (name "MANUFACTURER") "Panasonic") (field (name "MPN") "ERJ-2RKF2001X"))
      (libsource (lib "eagle-import") (part "RESISTOR0402_RES"))
    )
    (comp (ref "R28")
      (value "2 kΩ")
      (footprint "eagle-import:0402_RES")
      (description "RES SMD 2K OHM 1% 1/10W 0402")
      (fields (field (name "MANUFACTURER") "Panasonic") (field (name "MPN") "ERJ-2RKF2001X"))
      (libsource (lib "eagle-import") (part "RESISTOR0402_RES"))
    )
    (comp (ref "U6")
      (value "PCA9544AQFN-N20")
      (footprint "eagle-import:QFN-N20")
      (libsource (lib "eagle-import") (part "PCA9544AQFN-N20"))
    )
    (comp (ref "U8")
      (value "LTC2941")
      (footprint "eagle-import:DFN-6-2MMX3MM")
      (libsource (lib "eagle-import") (part "LTC2941"))
    )
    (comp (ref "U9")
      (value "LTC2943")
      (footprint "eagle-import:DFN-8")
      (libsource (lib "eagle-import") (part "LTC2943"))
    )
    (comp (ref "U10")
      (value "LTC2943")
      (footprint "eagle-import:DFN-8")
      (libsource (lib "eagle-import") (part "LTC2943"))
    )
    (comp (ref "U11")
      (value "LTC2943")
      (footprint "eagle-import:DFN-8")
      (libsource (lib "eagle-import") (part "LTC2943"))
    )
    (comp (ref "J3")
      (value "TC2030-FTDI-I2C")
      (footprint "eagle-import:TC2030-IDC-NL")
      (libsource (lib "eagle-import") (part "TC2030-FTDI-I2C"))
    )
    (comp (ref "JP1")
      (value "M04PTH")
      (footprint "eagle-import:1X04")
      (libsource (lib "eagle-import") (part "M04PTH"))
    )
    (comp (ref "TP1")
      (value "TEST_POINT_0.040IN")
      (footprint "eagle-import:TESTPOINT_0.040IN")
      (libsource (lib "eagle-import") (part "TEST_POINT_0.040IN"))
    )
    (comp (ref "TP2")
      (value "TEST_POINT_0.040IN")
      (footprint "eagle-import:TESTPOINT_0.040IN")
      (libsource (lib "eagle-import") (part "TEST_POINT_0.040IN"))
    )
    (comp (ref "TP3")
      (value "TEST_POINT_0.040IN")
      (footprint "eagle-import:TESTPOINT_0.040IN")
      (libsource (lib "eagle-import") (part "TEST_POINT_0.040IN"))
    )
    (comp (ref "TP4")
      (value "TEST_POINT_0.040IN")
      (footprint "eagle-import:TESTPOINT_0.040IN")
      (libsource (lib "eagle-import") (part "TEST_POINT_0.040IN"))
    )
    (comp (ref "TP5")
      (value "TEST_POINT_0.040IN")
      (footprint "eagle-import:TESTPOINT_0.040IN")
      (libsource (lib "eagle-import") (part "TEST_POINT_0.040IN"))
    )
    (comp (ref "TP6")
      (value "TEST_POINT_0.040IN")
      (footprint "eagle-import:TESTPOINT_0.040IN")
      (libsource (lib "eagle-import") (part "TEST_POINT_0.040IN"))
    )
    (comp (ref "TP7")
      (value "TEST_POINT_0.040IN")
      (footprint "eagle-import:TESTPOINT_0.040IN")
      (libsource (lib "eagle-import") (part "TEST_POINT_0.040IN"))
    )
    (comp (ref "TP8")
      (value "TEST_POINT_0.040IN")
      (footprint "eagle-import:TESTPOINT_0.040IN")
      (libsource (lib "eagle-import") (part "TEST_POINT_0.040IN"))
    )
    (comp (ref "H1")
      (value "MOUNT-PAD-ROUND3.0")
      (footprint "eagle-import:3,0-PAD")
      (libsource (lib "eagle-import") (part "MOUNT-PAD-ROUND3"))
    )
    (comp (ref "H2")
      (value "MOUNT-PAD-ROUND3.0")
      (footprint "eagle-import:3,0-PAD")
      (libsource (lib "eagle-import") (part "MOUNT-PAD-ROUND3"))
    )
    (comp (ref "H3")
      (value "MOUNT-PAD-ROUND3.0")
      (footprint "eagle-import:3,0-PAD")
      (libsource (lib "eagle-import") (part "MOUNT-PAD-ROUND3"))
    )
    (comp (ref "H4")
      (value "MOUNT-PAD-ROUND3.0")
      (footprint "eagle-import:3,0-PAD")
      (libsource (lib "eagle-import") (part "MOUNT-PAD-ROUND3"))
    )
    (comp (ref "J1")
      (value "MODULE_POWER")
      (footprint "eagle-import:MODULE_POWER")
      (libsource (lib "eagle-import") (part "MODULE_POWER"))
    )
    (comp (ref "C23")
      (value "0.1 uF")
      (footprint "eagle-import:0402_CAP")
      (description "CAP CER 0.1UF 25V X5R 0402")
      (fields (field (name "MANUFACTURER") "Murata") (field (name "MPN") "GRM155R61E104KA87D"))
      (libsource (lib "eagle-import") (part "CAPACITOR0402_CAP"))
    )
    (comp (ref "SJ1") (value "SJ") (footprint "eagle-import:SJ") (libsource (lib "eagle-import") (part "SJ")))
    (comp (ref "U29")
      (value "M24C01WMN")
      (footprint "eagle-import:SOIC-8")
      (libsource (lib "eagle-import") (part "M24C01WMN"))
    )
    (comp (ref "C14")
      (value "0.1 uF")
      (footprint "eagle-import:0402_CAP")
      (description "CAP CER 0.1UF 25V X5R 0402")
      (fields (field (name "MANUFACTURER") "Murata") (field (name "MPN") "GRM155R61E104KA87D"))
      (libsource (lib "eagle-import") (part "CAPACITOR0402_CAP"))
    )
    (comp (ref "C20")
      (value "0.1 uF")
      (footprint "eagle-import:0402_CAP")
      (description "CAP CER 0.1UF 25V X5R 0402")
      (fields (field (name "MANUFACTURER") "Murata") (field (name "MPN") "GRM155R61E104KA87D"))
      (libsource (lib "eagle-import") (part "CAPACITOR0402_CAP"))
    )
    (comp (ref "C21")
      (value "0.1 uF")
      (footprint "eagle-import:0402_CAP")
      (description "CAP CER 0.1UF 25V X5R 0402")
      (fields (field (name "MANUFACTURER") "Murata") (field (name "MPN") "GRM155R61E104KA87D"))
      (libsource (lib "eagle-import") (part "CAPACITOR0402_CAP"))
    )
    (comp (ref "C22")
      (value "0.1 uF")
      (footprint "eagle-import:0402_CAP")
      (description "CAP CER 0.1UF 25V X5R 0402")
      (fields (field (name "MANUFACTURER") "Murata") (field (name "MPN") "GRM155R61E104KA87D"))
      (libsource (lib "eagle-import") (part "CAPACITOR0402_CAP"))
    )
    (comp (ref "C24")
      (value "0.47 uF")
      (footprint "eagle-import:0402_CAP")
      (description "CAP CER 0.47UF 6.3V X5R 0402")
      (fields (field (name "MANUFACTURER") "Murata") (field (name "MPN") "GRM155R60J474KE19D"))
      (libsource (lib "eagle-import") (part "CAPACITOR0402_CAP"))
    )
    (comp (ref "C25")
      (value "0.47 uF")
      (footprint "eagle-import:0402_CAP")
      (description "CAP CER 0.47UF 6.3V X5R 0402")
      (fields (field (name "MANUFACTURER") "Murata") (field (name "MPN") "GRM155R60J474KE19D"))
      (libsource (lib "eagle-import") (part "CAPACITOR0402_CAP"))
    )
    (comp (ref "C26")
      (value "0.47 uF")
      (footprint "eagle-import:0402_CAP")
      (description "CAP CER 0.47UF 6.3V X5R 0402")
      (fields (field (name "MANUFACTURER") "Murata") (field (name "MPN") "GRM155R60J474KE19D"))
      (libsource (lib "eagle-import") (part "CAPACITOR0402_CAP"))
    )
    (comp (ref "C27")
      (value "0.82 uF")
      (footprint "eagle-import:0402_CAP")
      (description "CAP CER 0.82UF 6.3V X6S 0402")
      (fields (field (name "MANUFACTURER") "Murata") (field (name "MPN") "GRM155C80J824KE15D"))
      (libsource (lib "eagle-import") (part "CAPACITOR0402_CAP"))
    )
    (comp (ref "Q1")
      (value "MOSFET-NCHANNELSMD")
      (footprint "eagle-import:SOT23-3")
      (description "MOSFET N-CH 60V 0.115A SOT-23")
      (fields (field (name "MANUFACTURER") "ON Semiconductor") (field (name "MPN") "2N7002LT1G"))
      (libsource (lib "eagle-import") (part "MOSFET-NCHANNELSMD"))
    )
    (comp (ref "R1")
      (value "0.010 Ω")
      (footprint "eagle-import:0805_RES")
      (description "RES SMD 0.01 OHM 1% 1/2W 0805")
      (fields (field (name "MANUFACTURER") "Vishay Dale") (field (name "MPN") "WSLP0805R0100FEB"))
      (libsource (lib "eagle-import") (part "RESISTOR0805_RES"))
    )
    (comp (ref "R11")
      (value "0.05 Ω")
      (footprint "eagle-import:0805_RES")
      (description "RES SMD 0.05 OHM 1% 1/2W 0805")
      (fields (field (name "MANUFACTURER") "Vishay Dale") (field (name "MPN") "WSLP0805R0500FEB"))
      (libsource (lib "eagle-import") (part "RESISTOR0805_RES"))
    )
    (comp (ref "R13")
      (value "1 kΩ")
      (footprint "eagle-import:0402_RES")
      (description "RES SMD 1K OHM 5% 1/10W 0402")
      (fields (field (name "MANUFACTURER") "Panasonic") (field (name "MPN") "ERJ-2GEJ102X"))
      (libsource (lib "eagle-import") (part "RESISTOR0402_RES"))
    )
    (comp (ref "R41")
      (value "2 kΩ")
      (footprint "eagle-import:0402_RES")
      (description "RES SMD 2K OHM 1% 1/10W 0402")
      (fields (field (name "MANUFACTURER") "Panasonic") (field (name "MPN") "ERJ-2RKF2001X"))
      (libsource (lib "eagle-import") (part "RESISTOR0402_RES"))
    )
    (comp (ref "R42")
      (value "2 kΩ")
      (footprint "eagle-import:0402_RES")
      (description "RES SMD 2K OHM 1% 1/10W 0402")
      (fields (field (name "MANUFACTURER") "Panasonic") (field (name "MPN") "ERJ-2RKF2001X"))
      (libsource (lib "eagle-import") (part "RESISTOR0402_RES"))
    )
    (comp (ref "R43")
      (value "2 kΩ")
      (footprint "eagle-import:0402_RES")
      (description "RES SMD 2K OHM 1% 1/10W 0402")
      (fields (field (name "MANUFACTURER") "Panasonic") (field (name "MPN") "ERJ-2RKF2001X"))
      (libsource (lib "eagle-import") (part "RESISTOR0402_RES"))
    )
    (comp (ref "R54")
      (value "150 Ω")
      (footprint "eagle-import:0402_RES")
      (description "RES SMD 150 OHM 1% 1/10W 0402")
      (fields (field (name "MANUFACTURER") "Panasonic") (field (name "MPN") "ERJ-2RKF1500X"))
      (libsource (lib "eagle-import") (part "RESISTOR0402_RES"))
    )
    (comp (ref "R55")
      (value "150 Ω")
      (footprint "eagle-import:0402_RES")
      (description "RES SMD 150 OHM 1% 1/10W 0402")
      (fields (field (name "MANUFACTURER") "Panasonic") (field (name "MPN") "ERJ-2RKF1500X"))
      (libsource (lib "eagle-import") (part "RESISTOR0402_RES"))
    )
    (comp (ref "R66")
      (value "1 kΩ")
      (footprint "eagle-import:0402_RES")
      (description "RES SMD 1K OHM 5% 1/10W 0402")
      (fields (field (name "MANUFACTURER") "Panasonic") (field (name "MPN") "ERJ-2GEJ102X"))
      (libsource (lib "eagle-import") (part "RESISTOR0402_RES"))
    )
    (comp (ref "R70")
      (value "150 Ω")
      (footprint "eagle-import:0402_RES")
      (description "RES SMD 150 OHM 1% 1/10W 0402")
      (fields (field (name "MANUFACTURER") "Panasonic") (field (name "MPN") "ERJ-2RKF1500X"))
      (libsource (lib "eagle-import") (part "RESISTOR0402_RES"))
    )
    (comp (ref "S1")
      (value "TE_SSA12/SPDT")
      (footprint "eagle-import:TE_SSA12_SPDT")
      (libsource (lib "eagle-import") (part "TE_SSA12/SPDT"))
    )
    (comp (ref "S2")
      (value "PTS810SJ")
      (footprint "eagle-import:PTS810SJ")
      (libsource (lib "eagle-import") (part "PTS810SJ"))
    )
    (comp (ref "U18")
      (value "MAX17205")
      (footprint "eagle-import:14-TDFN")
      (libsource (lib "eagle-import") (part "MAX17205"))
    )
    (comp (ref "U19")
      (value "ESDR0502N")
      (footprint "eagle-import:UDFN-6")
      (libsource (lib "eagle-import") (part "ESDR0502N"))
    )
    (comp (ref "U25")
      (value "PCA9544AQFN-N20")
      (footprint "eagle-import:QFN-N20")
      (libsource (lib "eagle-import") (part "PCA9544AQFN-N20"))
    )
    (comp (ref "U26")
      (value "LTC2943")
      (footprint "eagle-import:DFN-8")
      (libsource (lib "eagle-import") (part "LTC2943"))
    )
    (comp (ref "U27")
      (value "MAX6746")
      (footprint "eagle-import:SOT-23-8")
      (libsource (lib "eagle-import") (part "MAX6746"))
    )
    (comp (ref "U28")
      (value "3.3V")
      (footprint "eagle-import:SOT-23")
      (description "IC REG LDO 3.3V 50MA SOT23-3")
      (fields
        (field (name "DIGIKEY") "ZMR330FCT-ND")
        (field (name "MANUFACTURER") "Diodes Inc.")
        (field (name "MPN") "ZMR330FTA")
      )
      (libsource (lib "eagle-import") (part "TILM34803.3V"))
    )
    (comp (ref "U30")
      (value "SN74AUP1T14DCKR")
      (footprint "eagle-import:SC70")
      (libsource (lib "eagle-import") (part "SN74AUP1T14DCKR"))
    )
    (comp (ref "C5")
      (value "0.1 uF")
      (footprint "eagle-import:0402_CAP")
      (description "CAP CER 0.1UF 25V X5R 0402")
      (fields (field (name "MANUFACTURER") "Murata") (field (name "MPN") "GRM155R61E104KA87D"))
      (libsource (lib "eagle-import") (part "CAPACITOR0402_CAP"))
    )
    (comp (ref "C6")
      (value "0.1 uF")
      (footprint "eagle-import:0402_CAP")
      (description "CAP CER 0.1UF 25V X5R 0402")
      (fields (field (name "MANUFACTURER") "Murata") (field (name "MPN") "GRM155R61E104KA87D"))
      (libsource (lib "eagle-import") (part "CAPACITOR0402_CAP"))
    )
    (comp (ref "C7")
      (value "0.1 uF")
      (footprint "eagle-import:0402_CAP")
      (description "CAP CER 0.1UF 25V X5R 0402")
      (fields (field (name "MANUFACTURER") "Murata") (field (name "MPN") "GRM155R61E104KA87D"))
      (libsource (lib "eagle-import") (part "CAPACITOR0402_CAP"))
    )
    (comp (ref "C8")
      (value "0.1 uF")
      (footprint "eagle-import:0402_CAP")
      (description "CAP CER 0.1UF 25V X5R 0402")
      (fields (field (name "MANUFACTURER") "Murata") (field (name "MPN") "GRM155R61E104KA87D"))
      (libsource (lib "eagle-import") (part "CAPACITOR0402_CAP"))
    )
    (comp (ref "R6")
      (value "0.017 Ω")
      (footprint "eagle-import:0805_RES")
      (description "RES SMD 0.017 OHM 1% 1/2W 0805")
      (fields (field (name "MANUFACTURER") "Vishay Dale") (field (name "MPN") "WSLP0805R0170FEB"))
      (libsource (lib "eagle-import") (part "RESISTOR0805_RES"))
    )
    (comp (ref "R7")
      (value "0.017 Ω")
      (footprint "eagle-import:0805_RES")
      (description "RES SMD 0.017 OHM 1% 1/2W 0805")
      (fields (field (name "MANUFACTURER") "Vishay Dale") (field (name "MPN") "WSLP0805R0170FEB"))
      (libsource (lib "eagle-import") (part "RESISTOR0805_RES"))
    )
    (comp (ref "R8")
      (value "0.017 Ω")
      (footprint "eagle-import:0805_RES")
      (description "RES SMD 0.017 OHM 1% 1/2W 0805")
      (fields (field (name "MANUFACTURER") "Vishay Dale") (field (name "MPN") "WSLP0805R0170FEB"))
      (libsource (lib "eagle-import") (part "RESISTOR0805_RES"))
    )
    (comp (ref "R9")
      (value "0.017 Ω")
      (footprint "eagle-import:0805_RES")
      (description "RES SMD 0.017 OHM 1% 1/2W 0805")
      (fields (field (name "MANUFACTURER") "Vishay Dale") (field (name "MPN") "WSLP0805R0170FEB"))
      (libsource (lib "eagle-import") (part "RESISTOR0805_RES"))
    )
    (comp (ref "R29")
      (value "2 kΩ")
      (footprint "eagle-import:0402_RES")
      (description "RES SMD 2K OHM 1% 1/10W 0402")
      (fields (field (name "MANUFACTURER") "Panasonic") (field (name "MPN") "ERJ-2RKF2001X"))
      (libsource (lib "eagle-import") (part "RESISTOR0402_RES"))
    )
    (comp (ref "R30")
      (value "2 kΩ")
      (footprint "eagle-import:0402_RES")
      (description "RES SMD 2K OHM 1% 1/10W 0402")
      (fields (field (name "MANUFACTURER") "Panasonic") (field (name "MPN") "ERJ-2RKF2001X"))
      (libsource (lib "eagle-import") (part "RESISTOR0402_RES"))
    )
    (comp (ref "R31")
      (value "2 kΩ")
      (footprint "eagle-import:0402_RES")
      (description "RES SMD 2K OHM 1% 1/10W 0402")
      (fields (field (name "MANUFACTURER") "Panasonic") (field (name "MPN") "ERJ-2RKF2001X"))
      (libsource (lib "eagle-import") (part "RESISTOR0402_RES"))
    )
    (comp (ref "R32")
      (value "2 kΩ")
      (footprint "eagle-import:0402_RES")
      (description "RES SMD 2K OHM 1% 1/10W 0402")
      (fields (field (name "MANUFACTURER") "Panasonic") (field (name "MPN") "ERJ-2RKF2001X"))
      (libsource (lib "eagle-import") (part "RESISTOR0402_RES"))
    )
    (comp (ref "R33")
      (value "2 kΩ")
      (footprint "eagle-import:0402_RES")
      (description "RES SMD 2K OHM 1% 1/10W 0402")
      (fields (field (name "MANUFACTURER") "Panasonic") (field (name "MPN") "ERJ-2RKF2001X"))
      (libsource (lib "eagle-import") (part "RESISTOR0402_RES"))
    )
    (comp (ref "R34")
      (value "2 kΩ")
      (footprint "eagle-import:0402_RES")
      (description "RES SMD 2K OHM 1% 1/10W 0402")
      (fields (field (name "MANUFACTURER") "Panasonic") (field (name "MPN") "ERJ-2RKF2001X"))
      (libsource (lib "eagle-import") (part "RESISTOR0402_RES"))
    )
    (comp (ref "R35")
      (value "2 kΩ")
      (footprint "eagle-import:0402_RES")
      (description "RES SMD 2K OHM 1% 1/10W 0402")
      (fields (field (name "MANUFACTURER") "Panasonic") (field (name "MPN") "ERJ-2RKF2001X"))
      (libsource (lib "eagle-import") (part "RESISTOR0402_RES"))
    )
    (comp (ref "R36")
      (value "2 kΩ")
      (footprint "eagle-import:0402_RES")
      (description "RES SMD 2K OHM 1% 1/10W 0402")
      (fields (field (name "MANUFACTURER") "Panasonic") (field (name "MPN") "ERJ-2RKF2001X"))
      (libsource (lib "eagle-import") (part "RESISTOR0402_RES"))
    )
    (comp (ref "R37")
      (value "2 kΩ")
      (footprint "eagle-import:0402_RES")
      (description "RES SMD 2K OHM 1% 1/10W 0402")
      (fields (field (name "MANUFACTURER") "Panasonic") (field (name "MPN") "ERJ-2RKF2001X"))
      (libsource (lib "eagle-import") (part "RESISTOR0402_RES"))
    )
    (comp (ref "R38")
      (value "2 kΩ")
      (footprint "eagle-import:0402_RES")
      (description "RES SMD 2K OHM 1% 1/10W 0402")
      (fields (field (name "MANUFACTURER") "Panasonic") (field (name "MPN") "ERJ-2RKF2001X"))
      (libsource (lib "eagle-import") (part "RESISTOR0402_RES"))
    )
    (comp (ref "R39")
      (value "2 kΩ")
      (footprint "eagle-import:0402_RES")
      (description "RES SMD 2K OHM 1% 1/10W 0402")
      (fields (field (name "MANUFACTURER") "Panasonic") (field (name "MPN") "ERJ-2RKF2001X"))
      (libsource (lib "eagle-import") (part "RESISTOR0402_RES"))
    )
    (comp (ref "R40")
      (value "2 kΩ")
      (footprint "eagle-import:0402_RES")
      (description "RES SMD 2K OHM 1% 1/10W 0402")
      (fields (field (name "MANUFACTURER") "Panasonic") (field (name "MPN") "ERJ-2RKF2001X"))
      (libsource (lib "eagle-import") (part "RESISTOR0402_RES"))
    )
    (comp (ref "U7")
      (value "PCA9544AQFN-N20")
      (footprint "eagle-import:QFN-N20")
      (libsource (lib "eagle-import") (part "PCA9544AQFN-N20"))
    )
    (comp (ref "U12")
      (value "LTC2943")
      (footprint "eagle-import:DFN-8")
      (libsource (lib "eagle-import") (part "LTC2943"))
    )
    (comp (ref "U13")
      (value "LTC2943")
      (footprint "eagle-import:DFN-8")
      (libsource (lib "eagle-import") (part "LTC2943"))
    )
    (comp (ref "U14")
      (value "LTC2943")
      (footprint "eagle-import:DFN-8")
      (libsource (lib "eagle-import") (part "LTC2943"))
    )
    (comp (ref "U15")
      (value "LTC2943")
      (footprint "eagle-import:DFN-8")
      (libsource (lib "eagle-import") (part "LTC2943"))
    )
    (comp (ref "C28")
      (value "1 uF")
      (footprint "eagle-import:0603_CAP")
      (description "CAP CER 1UF 10V X5R 0603")
      (fields (field (name "MANUFACTURER") "Murata") (field (name "MPN") "GRM188R61A105KA61D"))
      (libsource (lib "eagle-import") (part "CAPACITOR0603_CAP"))
    )
    (comp (ref "C39")
      (value "10 uF")
      (footprint "eagle-import:0805_CAP")
      (description "CAP CER 10UF 25V 10% X5R 0805")
      (fields (field (name "MANUFACTURER") "Murata") (field (name "MPN") "GRM21BR61E106KA73L"))
      (libsource (lib "eagle-import") (part "CAPACITOR0805_CAP"))
    )
    (comp (ref "C40")
      (value "10 uF")
      (footprint "eagle-import:0805_CAP")
      (description "CAP CER 10UF 25V 10% X5R 0805")
      (fields (field (name "MANUFACTURER") "Murata") (field (name "MPN") "GRM21BR61E106KA73L"))
      (libsource (lib "eagle-import") (part "CAPACITOR0805_CAP"))
    )
    (comp (ref "D1")
      (value "DIODE_SCHOTTKYSOT-23F")
      (footprint "eagle-import:SOT-23F")
      (description "DIODE SCHOTTKY 40V 1.75A SOT23F")
      (fields (field (name "MANUFACTURER") "Central Semiconductor") (field (name "MPN") "CMPSH1-4 TR"))
      (libsource (lib "eagle-import") (part "DIODE_SCHOTTKYSOT-23F"))
    )
    (comp (ref "D2")
      (value "DIODE_ZENERSOT323")
      (footprint "eagle-import:SOD323")
      (description "DIODE ZENER 3.6V 400MW SOD323")
      (fields (field (name "MANUFACTURER") "NXP Semiconductors") (field (name "MPN") "PDZ3.6B,115"))
      (libsource (lib "eagle-import") (part "DIODE_ZENERSOT323"))
    )
    (comp (ref "D3")
      (value "DIODE_SCHOTTKYSOD323")
      (footprint "eagle-import:SOD323")
      (description "DIODE SCHOTTKY 40V 200MA SOD323")
      (fields (field (name "MANUFACTURER") "Central Semiconductor") (field (name "MPN") "CMDSH2-4L TR"))
      (libsource (lib "eagle-import") (part "DIODE_SCHOTTKYSOD323"))
    )
    (comp (ref "L6")
      (value "6.8uH")
      (footprint "eagle-import:IHL-2525CZ")
      (description "FIXED IND 6.8UH 5.5A 46.8 MOHM")
      (fields (field (name "MANUFACTURER") "Vishay Dale") (field (name "MPN") "IHLP2525CZER6R8M11"))
      (libsource (lib "eagle-import") (part "INDUCTORIHL2525CZ"))
    )
    (comp (ref "R10")
      (value "0.05 Ω")
      (footprint "eagle-import:0805_RES")
      (description "RES SMD 0.05 OHM 1% 1/2W 0805")
      (fields (field (name "MANUFACTURER") "Vishay Dale") (field (name "MPN") "WSLP0805R0500FEB"))
      (libsource (lib "eagle-import") (part "RESISTOR0805_RES"))
    )
    (comp (ref "R12")
      (value "1 kΩ")
      (footprint "eagle-import:0402_RES")
      (description "RES SMD 1K OHM 5% 1/10W 0402")
      (fields (field (name "MANUFACTURER") "Panasonic") (field (name "MPN") "ERJ-2GEJ102X"))
      (libsource (lib "eagle-import") (part "RESISTOR0402_RES"))
    )
    (comp (ref "R15")
      (value "1 MΩ")
      (footprint "eagle-import:0402_RES")
      (description "RES SMD 1M OHM 1% 1/10W 0402")
      (fields (field (name "MANUFACTURER") "Panasonic") (field (name "MPN") "ERJ-2RKF1004X"))
      (libsource (lib "eagle-import") (part "RESISTOR0402_RES"))
    )
    (comp (ref "R16")
      (value "1 MΩ")
      (footprint "eagle-import:0402_RES")
      (description "RES SMD 1M OHM 1% 1/10W 0402")
      (fields (field (name "MANUFACTURER") "Panasonic") (field (name "MPN") "ERJ-2RKF1004X"))
      (libsource (lib "eagle-import") (part "RESISTOR0402_RES"))
    )
    (comp (ref "R44")
      (value "23.2 kΩ")
      (footprint "eagle-import:0805_RES")
      (description "RES SMD 23.2K OHM 0.1% 1/8W 0805")
      (fields (field (name "MANUFACTURER") "Panasonic") (field (name "MPN") "ERA6AEB2322V"))
      (libsource (lib "eagle-import") (part "RESISTOR0805_RES"))
    )
    (comp (ref "R57")
      (value "301 kΩ")
      (footprint "eagle-import:0805_RES")
      (description "RES SMD 301K OHM 0.1% 1/8W 0805")
      (fields (field (name "MANUFACTURER") "Panasonic") (field (name "MPN") "ERA-6AEB3013V"))
      (libsource (lib "eagle-import") (part "RESISTOR0805_RES"))
    )
    (comp (ref "R58")
      (value "340 kΩ")
      (footprint "eagle-import:0805_RES")
      (description "RES SMD 340K OHM 0.1% 1/8W 0805")
      (fields (field (name "MANUFACTURER") "Panasonic") (field (name "MPN") "ERA-6AEB3403V"))
      (libsource (lib "eagle-import") (part "RESISTOR0805_RES"))
    )
    (comp (ref "R64")
      (value "953 kΩ")
      (footprint "eagle-import:0805_RES")
      (description "RES SMD 953K OHM 0.1% 1/8W 0805")
      (fields (field (name "MANUFACTURER") "Panasonic") (field (name "MPN") "ERA-6AEB9533V"))
      (libsource (lib "eagle-import") (part "RESISTOR0805_RES"))
    )
    (comp (ref "U16")
      (value "LT3652")
      (footprint "eagle-import:DFN-12_3MM")
      (libsource (lib "eagle-import") (part "LT3652"))
    )
    (comp (ref "U17")
      (value "LM234")
      (footprint "eagle-import:SOIC-8")
      (libsource (lib "eagle-import") (part "LM234"))
    )
  )
  (nets
    (net (code "1") (name "CHRG") (class "Default")
      (node (ref "R16") (pin "1") (pinfunction "1_1") (pintype "passive"))
      (node (ref "TP7") (pin "TESTPOINT") (pinfunction "TESTPOINT_TESTPOINT") (pintype "bidirectional"))
      (node (ref "U16") (pin "4") (pinfunction "~{CHRG}_4") (pintype "bidirectional"))
    )
    (net (code "2") (name "CHRG_FAULT") (class "Default")
      (node (ref "R15") (pin "1") (pinfunction "1_1") (pintype "passive"))
      (node (ref "TP6") (pin "TESTPOINT") (pinfunction "TESTPOINT_TESTPOINT") (pintype "bidirectional"))
      (node (ref "U16") (pin "5") (pinfunction "~{FAULT}_5") (pintype "bidirectional"))
    )
    (net (code "3") (name "GND") (class "Default")
      (node (ref "C1") (pin "2") (pinfunction "2_2") (pintype "bidirectional"))
      (node (ref "C10") (pin "2") (pinfunction "2_2") (pintype "bidirectional"))
      (node (ref "C11") (pin "2") (pinfunction "2_2") (pintype "bidirectional"))
      (node (ref "C12") (pin "2") (pinfunction "2_2") (pintype "bidirectional"))
      (node (ref "C13") (pin "2") (pinfunction "2_2") (pintype "bidirectional"))
      (node (ref "C14") (pin "2") (pinfunction "2_2") (pintype "bidirectional"))
      (node (ref "C15") (pin "2") (pinfunction "2_2") (pintype "bidirectional"))
      (node (ref "C16") (pin "2") (pinfunction "2_2") (pintype "bidirectional"))
      (node (ref "C17") (pin "2") (pinfunction "2_2") (pintype "bidirectional"))
      (node (ref "C18") (pin "2") (pinfunction "2_2") (pintype "bidirectional"))
      (node (ref "C19") (pin "2") (pinfunction "2_2") (pintype "bidirectional"))
      (node (ref "C2") (pin "2") (pinfunction "2_2") (pintype "bidirectional"))
      (node (ref "C20") (pin "2") (pinfunction "2_2") (pintype "bidirectional"))
      (node (ref "C21") (pin "2") (pinfunction "2_2") (pintype "bidirectional"))
      (node (ref "C22") (pin "2") (pinfunction "2_2") (pintype "bidirectional"))
      (node (ref "C23") (pin "2") (pinfunction "2_2") (pintype "bidirectional"))
      (node (ref "C24") (pin "2") (pinfunction "2_2") (pintype "bidirectional"))
      (node (ref "C25") (pin "2") (pinfunction "2_2") (pintype "bidirectional"))
      (node (ref "C26") (pin "2") (pinfunction "2_2") (pintype "bidirectional"))
      (node (ref "C27") (pin "2") (pinfunction "2_2") (pintype "bidirectional"))
      (node (ref "C29") (pin "1") (pinfunction "1_1") (pintype "bidirectional"))
      (node (ref "C3") (pin "2") (pinfunction "2_2") (pintype "bidirectional"))
      (node (ref "C30") (pin "1") (pinfunction "1_1") (pintype "bidirectional"))
      (node (ref "C31") (pin "1") (pinfunction "1_1") (pintype "bidirectional"))
      (node (ref "C32") (pin "1") (pinfunction "1_1") (pintype "bidirectional"))
      (node (ref "C33") (pin "1") (pinfunction "1_1") (pintype "bidirectional"))
      (node (ref "C34") (pin "P$2") (pinfunction "2_P$2") (pintype "bidirectional"))
      (node (ref "C35") (pin "P$2") (pinfunction "2_P$2") (pintype "bidirectional"))
      (node (ref "C36") (pin "P$2") (pinfunction "2_P$2") (pintype "bidirectional"))
      (node (ref "C37") (pin "P$2") (pinfunction "2_P$2") (pintype "bidirectional"))
      (node (ref "C38") (pin "P$2") (pinfunction "2_P$2") (pintype "bidirectional"))
      (node (ref "C39") (pin "P$2") (pinfunction "2_P$2") (pintype "bidirectional"))
      (node (ref "C4") (pin "2") (pinfunction "2_2") (pintype "bidirectional"))
      (node (ref "C40") (pin "P$2") (pinfunction "2_P$2") (pintype "bidirectional"))
      (node (ref "C41") (pin "1") (pinfunction "1_1") (pintype "bidirectional"))
      (node (ref "C42") (pin "1") (pinfunction "1_1") (pintype "bidirectional"))
      (node (ref "C43") (pin "1") (pinfunction "1_1") (pintype "bidirectional"))
      (node (ref "C44") (pin "1") (pinfunction "1_1") (pintype "bidirectional"))
      (node (ref "C45") (pin "1") (pinfunction "1_1") (pintype "bidirectional"))
      (node (ref "C46") (pin "1") (pinfunction "1_1") (pintype "bidirectional"))
      (node (ref "C47") (pin "1") (pinfunction "1_1") (pintype "bidirectional"))
      (node (ref "C48") (pin "1") (pinfunction "1_1") (pintype "bidirectional"))
      (node (ref "C49") (pin "1") (pinfunction "1_1") (pintype "bidirectional"))
      (node (ref "C5") (pin "2") (pinfunction "2_2") (pintype "bidirectional"))
      (node (ref "C50") (pin "1") (pinfunction "1_1") (pintype "bidirectional"))
      (node (ref "C6") (pin "2") (pinfunction "2_2") (pintype "bidirectional"))
      (node (ref "C7") (pin "2") (pinfunction "2_2") (pintype "bidirectional"))
      (node (ref "C8") (pin "2") (pinfunction "2_2") (pintype "bidirectional"))
      (node (ref "C9") (pin "2") (pinfunction "2_2") (pintype "bidirectional"))
      (node (ref "D1") (pin "P$1") (pinfunction "ANODE_P$1") (pintype "bidirectional"))
      (node (ref "H1") (pin "B3,0") (pinfunction "MOUNT_B3,0") (pintype "passive"))
      (node (ref "H2") (pin "B3,0") (pinfunction "MOUNT_B3,0") (pintype "passive"))
      (node (ref "H3") (pin "B3,0") (pinfunction "MOUNT_B3,0") (pintype "passive"))
      (node (ref "H4") (pin "B3,0") (pinfunction "MOUNT_B3,0") (pintype "passive"))
      (node (ref "J1") (pin "1") (pinfunction "GND_1") (pintype "power_in"))
      (node (ref "J1") (pin "20") (pinfunction "VSOL-_20") (pintype "power_in"))
      (node (ref "J3") (pin "3") (pinfunction "GND_3") (pintype "bidirectional"))
      (node (ref "JP1") (pin "1") (pinfunction "1_1") (pintype "passive"))
      (node (ref "R1") (pin "2") (pinfunction "2_2") (pintype "passive"))
      (node (ref "R44") (pin "1") (pinfunction "1_1") (pintype "passive"))
      (node (ref "R50") (pin "1") (pinfunction "1_1") (pintype "passive"))
      (node (ref "R51") (pin "1") (pinfunction "1_1") (pintype "passive"))
      (node (ref "R52") (pin "1") (pinfunction "1_1") (pintype "passive"))
      (node (ref "R53") (pin "1") (pinfunction "1_1") (pintype "passive"))
      (node (ref "R56") (pin "1") (pinfunction "1_1") (pintype "passive"))
      (node (ref "R58") (pin "2") (pinfunction "2_2") (pintype "passive"))
      (node (ref "R66") (pin "1") (pinfunction "1_1") (pintype "passive"))
      (node (ref "S1") (pin "1") (pinfunction "A_1") (pintype "bidirectional"))
      (node (ref "S2") (pin "3") (pinfunction "P$2_3") (pintype "passive"))
      (node (ref "S2") (pin "4") (pinfunction "P$2_4") (pintype "passive"))
      (node (ref "U1") (pin "15") (pinfunction "PGND_15") (pintype "bidirectional"))
      (node (ref "U1") (pin "16") (pinfunction "PGND_16") (pintype "bidirectional"))
      (node (ref "U1") (pin "6") (pinfunction "AGND_6") (pintype "bidirectional"))
      (node (ref "U1") (pin "7") (pinfunction "FSW_7") (pintype "bidirectional"))
      (node (ref "U1") (pin "8") (pinfunction "DEF_8") (pintype "bidirectional"))
      (node (ref "U1") (pin "GND") (pinfunction "PGND_GND") (pintype "bidirectional"))
      (node (ref "U10") (pin "P$1") (pinfunction "GND_P$1") (pintype "open_collector"))
      (node (ref "U10") (pin "P2") (pinfunction "GND_P2") (pintype "open_collector"))
      (node (ref "U10") (pin "P3") (pinfunction "GND_P3") (pintype "open_collector"))
      (node (ref "U10") (pin "P7") (pinfunction "GND_P7") (pintype "open_collector"))
      (node (ref "U11") (pin "P$1") (pinfunction "GND_P$1") (pintype "open_collector"))
      (node (ref "U11") (pin "P2") (pinfunction "GND_P2") (pintype "open_collector"))
      (node (ref "U11") (pin "P3") (pinfunction "GND_P3") (pintype "open_collector"))
      (node (ref "U11") (pin "P7") (pinfunction "GND_P7") (pintype "open_collector"))
      (node (ref "U12") (pin "P$1") (pinfunction "GND_P$1") (pintype "open_collector"))
      (node (ref "U12") (pin "P2") (pinfunction "GND_P2") (pintype "open_collector"))
      (node (ref "U12") (pin "P3") (pinfunction "GND_P3") (pintype "open_collector"))
      (node (ref "U12") (pin "P7") (pinfunction "GND_P7") (pintype "open_collector"))
      (node (ref "U13") (pin "P$1") (pinfunction "GND_P$1") (pintype "open_collector"))
      (node (ref "U13") (pin "P2") (pinfunction "GND_P2") (pintype "open_collector"))
      (node (ref "U13") (pin "P3") (pinfunction "GND_P3") (pintype "open_collector"))
      (node (ref "U13") (pin "P7") (pinfunction "GND_P7") (pintype "open_collector"))
      (node (ref "U14") (pin "P$1") (pinfunction "GND_P$1") (pintype "open_collector"))
      (node (ref "U14") (pin "P2") (pinfunction "GND_P2") (pintype "open_collector"))
      (node (ref "U14") (pin "P3") (pinfunction "GND_P3") (pintype "open_collector"))
      (node (ref "U14") (pin "P7") (pinfunction "GND_P7") (pintype "open_collector"))
      (node (ref "U15") (pin "P$1") (pinfunction "GND_P$1") (pintype "open_collector"))
      (node (ref "U15") (pin "P2") (pinfunction "GND_P2") (pintype "open_collector"))
      (node (ref "U15") (pin "P3") (pinfunction "GND_P3") (pintype "open_collector"))
      (node (ref "U15") (pin "P7") (pinfunction "GND_P7") (pintype "open_collector"))
      (node (ref "U16") (pin "13") (pinfunction "GND_13") (pintype "bidirectional"))
      (node (ref "U16") (pin "6") (pinfunction "TIMER_6") (pintype "bidirectional"))
      (node (ref "U18") (pin "13") (pinfunction "CELLX_13") (pintype "bidirectional"))
      (node (ref "U18") (pin "15") (pinfunction "CSN_15") (pintype "bidirectional"))
      (node (ref "U18") (pin "4") (pinfunction "CSN_4") (pintype "bidirectional"))
      (node (ref "U18") (pin "6") (pinfunction "CELL2_6") (pintype "bidirectional"))
      (node (ref "U18") (pin "7") (pinfunction "CELL1_7") (pintype "bidirectional"))
      (node (ref "U19") (pin "P$1") (pinfunction "GND_P$1") (pintype "bidirectional"))
      (node (ref "U2") (pin "15") (pinfunction "PGND_15") (pintype "bidirectional"))
      (node (ref "U2") (pin "16") (pinfunction "PGND_16") (pintype "bidirectional"))
      (node (ref "U2") (pin "6") (pinfunction "AGND_6") (pintype "bidirectional"))
      (node (ref "U2") (pin "7") (pinfunction "FSW_7") (pintype "bidirectional"))
      (node (ref "U2") (pin "8") (pinfunction "DEF_8") (pintype "bidirectional"))
      (node (ref "U2") (pin "GND") (pinfunction "PGND_GND") (pintype "bidirectional"))
      (node (ref "U20") (pin "2") (pinfunction "GND_2") (pintype "bidirectional"))
      (node (ref "U21") (pin "2") (pinfunction "GND_2") (pintype "bidirectional"))
      (node (ref "U22") (pin "2") (pinfunction "GND_2") (pintype "bidirectional"))
      (node (ref "U23") (pin "2") (pinfunction "GND_2") (pintype "bidirectional"))
      (node (ref "U24") (pin "2") (pinfunction "GND_2") (pintype "bidirectional"))
      (node (ref "U25") (pin "1") (pinfunction "A0_1") (pintype "bidirectional"))
      (node (ref "U25") (pin "10") (pinfunction "GND_10") (pintype "bidirectional"))
      (node (ref "U25") (pin "3") (pinfunction "A2_3") (pintype "bidirectional"))
      (node (ref "U26") (pin "P$1") (pinfunction "GND_P$1") (pintype "open_collector"))
      (node (ref "U26") (pin "P2") (pinfunction "GND_P2") (pintype "open_collector"))
      (node (ref "U26") (pin "P3") (pinfunction "GND_P3") (pintype "open_collector"))
      (node (ref "U26") (pin "P7") (pinfunction "GND_P7") (pintype "open_collector"))
      (node (ref "U27") (pin "4") (pinfunction "GND_4") (pintype "bidirectional"))
      (node (ref "U28") (pin "3") (pinfunction "GND_3") (pintype "bidirectional"))
      (node (ref "U29") (pin "1") (pinfunction "E0_1") (pintype "bidirectional"))
      (node (ref "U29") (pin "2") (pinfunction "E1_2") (pintype "bidirectional"))
      (node (ref "U29") (pin "3") (pinfunction "E2_3") (pintype "bidirectional"))
      (node (ref "U29") (pin "4") (pinfunction "GND_4") (pintype "bidirectional"))
      (node (ref "U3") (pin "15") (pinfunction "PGND_15") (pintype "bidirectional"))
      (node (ref "U3") (pin "16") (pinfunction "PGND_16") (pintype "bidirectional"))
      (node (ref "U3") (pin "6") (pinfunction "AGND_6") (pintype "bidirectional"))
      (node (ref "U3") (pin "7") (pinfunction "FSW_7") (pintype "bidirectional"))
      (node (ref "U3") (pin "8") (pinfunction "DEF_8") (pintype "bidirectional"))
      (node (ref "U3") (pin "GND") (pinfunction "PGND_GND") (pintype "bidirectional"))
      (node (ref "U30") (pin "3") (pinfunction "GND_3") (pintype "bidirectional"))
      (node (ref "U4") (pin "15") (pinfunction "PGND_15") (pintype "bidirectional"))
      (node (ref "U4") (pin "16") (pinfunction "PGND_16") (pintype "bidirectional"))
      (node (ref "U4") (pin "6") (pinfunction "AGND_6") (pintype "bidirectional"))
      (node (ref "U4") (pin "7") (pinfunction "FSW_7") (pintype "bidirectional"))
      (node (ref "U4") (pin "8") (pinfunction "DEF_8") (pintype "bidirectional"))
      (node (ref "U4") (pin "GND") (pinfunction "PGND_GND") (pintype "bidirectional"))
      (node (ref "U5") (pin "15") (pinfunction "PGND_15") (pintype "bidirectional"))
      (node (ref "U5") (pin "16") (pinfunction "PGND_16") (pintype "bidirectional"))
      (node (ref "U5") (pin "6") (pinfunction "AGND_6") (pintype "bidirectional"))
      (node (ref "U5") (pin "7") (pinfunction "FSW_7") (pintype "bidirectional"))
      (node (ref "U5") (pin "8") (pinfunction "DEF_8") (pintype "bidirectional"))
      (node (ref "U5") (pin "GND") (pinfunction "PGND_GND") (pintype "bidirectional"))
      (node (ref "U6") (pin "1") (pinfunction "A0_1") (pintype "bidirectional"))
      (node (ref "U6") (pin "10") (pinfunction "GND_10") (pintype "bidirectional"))
      (node (ref "U6") (pin "2") (pinfunction "A1_2") (pintype "bidirectional"))
      (node (ref "U6") (pin "3") (pinfunction "A2_3") (pintype "bidirectional"))
      (node (ref "U7") (pin "10") (pinfunction "GND_10") (pintype "bidirectional"))
      (node (ref "U7") (pin "2") (pinfunction "A1_2") (pintype "bidirectional"))
      (node (ref "U7") (pin "3") (pinfunction "A2_3") (pintype "bidirectional"))
      (node (ref "U8") (pin "2") (pinfunction "GND_2") (pintype "open_collector"))
      (node (ref "U9") (pin "P$1") (pinfunction "GND_P$1") (pintype "open_collector"))
      (node (ref "U9") (pin "P2") (pinfunction "GND_P2") (pintype "open_collector"))
      (node (ref "U9") (pin "P3") (pinfunction "GND_P3") (pintype "open_collector"))
      (node (ref "U9") (pin "P7") (pinfunction "GND_P7") (pintype "open_collector"))
    )
    (net (code "4") (name "Net-(D1-CATHODE)") (class "Default")
      (node (ref "C28") (pin "1") (pinfunction "1_1") (pintype "bidirectional"))
      (node (ref "D1") (pin "P$3") (pinfunction "CATHODE_P$3") (pintype "bidirectional"))
      (node (ref "L6") (pin "P$1") (pinfunction "1_P$1") (pintype "bidirectional"))
      (node (ref "U16") (pin "12") (pinfunction "SW_12") (pintype "bidirectional"))
    )
    (net (code "5") (name "Net-(D2-ANODE)") (class "Default")
      (node (ref "D2") (pin "P$2") (pinfunction "ANODE_P$2") (pintype "bidirectional"))
      (node (ref "D3") (pin "P$2") (pinfunction "ANODE_P$2") (pintype "bidirectional"))
    )
    (net (code "6") (name "Net-(D3-CATHODE)") (class "Default")
      (node (ref "C28") (pin "2") (pinfunction "2_2") (pintype "bidirectional"))
      (node (ref "D3") (pin "P$1") (pinfunction "CATHODE_P$1") (pintype "bidirectional"))
      (node (ref "U16") (pin "11") (pinfunction "BOOST_11") (pintype "bidirectional"))
    )
    (net (code "7") (name "Net-(L1-1)") (class "Default")
      (node (ref "L1") (pin "P$1") (pinfunction "1_P$1") (pintype "bidirectional"))
      (node (ref "U1") (pin "1") (pinfunction "SW_1") (pintype "bidirectional"))
      (node (ref "U1") (pin "2") (pinfunction "SW_2") (pintype "bidirectional"))
      (node (ref "U1") (pin "3") (pinfunction "SW_3") (pintype "bidirectional"))
    )
    (net (code "8") (name "Net-(L1-2)") (class "Default")
      (node (ref "C42") (pin "2") (pinfunction "2_2") (pintype "bidirectional"))
      (node (ref "L1") (pin "P$2") (pinfunction "2_P$2") (pintype "bidirectional"))
      (node (ref "R46") (pin "2") (pinfunction "2_2") (pintype "passive"))
      (node (ref "R59") (pin "2") (pinfunction "2_2") (pintype "passive"))
      (node (ref "U1") (pin "14") (pinfunction "VOS_14") (pintype "bidirectional"))
      (node (ref "U21") (pin "1") (pinfunction "IN_1") (pintype "bidirectional"))
      (node (ref "U21") (pin "3") (pinfunction "EN_3") (pintype "bidirectional"))
    )
    (net (code "9") (name "Net-(L2-1)") (class "Default")
      (node (ref "L2") (pin "P$1") (pinfunction "1_P$1") (pintype "bidirectional"))
      (node (ref "U2") (pin "1") (pinfunction "SW_1") (pintype "bidirectional"))
      (node (ref "U2") (pin "2") (pinfunction "SW_2") (pintype "bidirectional"))
      (node (ref "U2") (pin "3") (pinfunction "SW_3") (pintype "bidirectional"))
    )
    (net (code "10") (name "Net-(L2-2)") (class "Default")
      (node (ref "C43") (pin "2") (pinfunction "2_2") (pintype "bidirectional"))
      (node (ref "L2") (pin "P$2") (pinfunction "2_P$2") (pintype "bidirectional"))
      (node (ref "R47") (pin "2") (pinfunction "2_2") (pintype "passive"))
      (node (ref "R60") (pin "2") (pinfunction "2_2") (pintype "passive"))
      (node (ref "U2") (pin "14") (pinfunction "VOS_14") (pintype "bidirectional"))
      (node (ref "U22") (pin "1") (pinfunction "IN_1") (pintype "bidirectional"))
      (node (ref "U22") (pin "3") (pinfunction "EN_3") (pintype "bidirectional"))
    )
    (net (code "11") (name "Net-(L3-1)") (class "Default")
      (node (ref "L3") (pin "P$1") (pinfunction "1_P$1") (pintype "bidirectional"))
      (node (ref "U3") (pin "1") (pinfunction "SW_1") (pintype "bidirectional"))
      (node (ref "U3") (pin "2") (pinfunction "SW_2") (pintype "bidirectional"))
      (node (ref "U3") (pin "3") (pinfunction "SW_3") (pintype "bidirectional"))
    )
    (net (code "12") (name "Net-(L3-2)") (class "Default")
      (node (ref "C44") (pin "2") (pinfunction "2_2") (pintype "bidirectional"))
      (node (ref "L3") (pin "P$2") (pinfunction "2_P$2") (pintype "bidirectional"))
      (node (ref "R48") (pin "2") (pinfunction "2_2") (pintype "passive"))
      (node (ref "R61") (pin "2") (pinfunction "2_2") (pintype "passive"))
      (node (ref "U23") (pin "1") (pinfunction "IN_1") (pintype "bidirectional"))
      (node (ref "U23") (pin "3") (pinfunction "EN_3") (pintype "bidirectional"))
      (node (ref "U3") (pin "14") (pinfunction "VOS_14") (pintype "bidirectional"))
    )
    (net (code "13") (name "Net-(L4-1)") (class "Default")
      (node (ref "L4") (pin "P$1") (pinfunction "1_P$1") (pintype "bidirectional"))
      (node (ref "U4") (pin "1") (pinfunction "SW_1") (pintype "bidirectional"))
      (node (ref "U4") (pin "2") (pinfunction "SW_2") (pintype "bidirectional"))
      (node (ref "U4") (pin "3") (pinfunction "SW_3") (pintype "bidirectional"))
    )
    (net (code "14") (name "Net-(L4-2)") (class "Default")
      (node (ref "C41") (pin "2") (pinfunction "2_2") (pintype "bidirectional"))
      (node (ref "L4") (pin "P$2") (pinfunction "2_P$2") (pintype "bidirectional"))
      (node (ref "R45") (pin "2") (pinfunction "2_2") (pintype "passive"))
      (node (ref "R63") (pin "2") (pinfunction "2_2") (pintype "passive"))
      (node (ref "U20") (pin "1") (pinfunction "IN_1") (pintype "bidirectional"))
      (node (ref "U20") (pin "3") (pinfunction "EN_3") (pintype "bidirectional"))
      (node (ref "U4") (pin "14") (pinfunction "VOS_14") (pintype "bidirectional"))
    )
    (net (code "15") (name "Net-(L5-1)") (class "Default")
      (node (ref "L5") (pin "P$1") (pinfunction "1_P$1") (pintype "bidirectional"))
      (node (ref "U5") (pin "1") (pinfunction "SW_1") (pintype "bidirectional"))
      (node (ref "U5") (pin "2") (pinfunction "SW_2") (pintype "bidirectional"))
      (node (ref "U5") (pin "3") (pinfunction "SW_3") (pintype "bidirectional"))
    )
    (net (code "16") (name "Net-(L5-2)") (class "Default")
      (node (ref "C45") (pin "2") (pinfunction "2_2") (pintype "bidirectional"))
      (node (ref "L5") (pin "P$2") (pinfunction "2_P$2") (pintype "bidirectional"))
      (node (ref "R49") (pin "2") (pinfunction "2_2") (pintype "passive"))
      (node (ref "R62") (pin "2") (pinfunction "2_2") (pintype "passive"))
      (node (ref "U24") (pin "1") (pinfunction "IN_1") (pintype "bidirectional"))
      (node (ref "U24") (pin "3") (pinfunction "EN_3") (pintype "bidirectional"))
      (node (ref "U5") (pin "14") (pinfunction "VOS_14") (pintype "bidirectional"))
    )
    (net (code "17") (name "Net-(L6-2)") (class "Default")
      (node (ref "L6") (pin "P$2") (pinfunction "2_P$2") (pintype "bidirectional"))
      (node (ref "R10") (pin "1") (pinfunction "1_1") (pintype "passive"))
      (node (ref "U16") (pin "10") (pinfunction "SENSE_10") (pintype "bidirectional"))
    )
    (net (code "18") (name "Net-(Q1-G)") (class "Default")
      (node (ref "Q1") (pin "1") (pinfunction "G_1") (pintype "passive"))
      (node (ref "R70") (pin "2") (pinfunction "2_2") (pintype "passive"))
    )
    (net (code "19") (name "Net-(Q1-S)") (class "Default")
      (node (ref "Q1") (pin "2") (pinfunction "S_2") (pintype "passive"))
      (node (ref "R66") (pin "2") (pinfunction "2_2") (pintype "passive"))
    )
    (net (code "20") (name "Net-(S1-B)") (class "Default")
      (node (ref "C26") (pin "1") (pinfunction "1_1") (pintype "bidirectional"))
      (node (ref "S1") (pin "2") (pinfunction "B_2") (pintype "bidirectional"))
    )
    (net (code "21") (name "Net-(U1-FB)") (class "Default")
      (node (ref "R50") (pin "2") (pinfunction "2_2") (pintype "passive"))
      (node (ref "R59") (pin "1") (pinfunction "1_1") (pintype "passive"))
      (node (ref "U1") (pin "5") (pinfunction "FB_5") (pintype "bidirectional"))
    )
    (net (code "22") (name "Net-(U1-PG)") (class "Default")
      (node (ref "R46") (pin "1") (pinfunction "1_1") (pintype "passive"))
      (node (ref "U1") (pin "4") (pinfunction "PG_4") (pintype "bidirectional"))
    )
    (net (code "23") (name "Net-(U1-SS{slash}TR)") (class "Default")
      (node (ref "C30") (pin "2") (pinfunction "2_2") (pintype "bidirectional"))
      (node (ref "U1") (pin "9") (pinfunction "SS/TR_9") (pintype "bidirectional"))
    )
    (net (code "24") (name "Net-(U2-FB)") (class "Default")
      (node (ref "R51") (pin "2") (pinfunction "2_2") (pintype "passive"))
      (node (ref "R60") (pin "1") (pinfunction "1_1") (pintype "passive"))
      (node (ref "U2") (pin "5") (pinfunction "FB_5") (pintype "bidirectional"))
    )
    (net (code "25") (name "Net-(U2-PG)") (class "Default")
      (node (ref "R47") (pin "1") (pinfunction "1_1") (pintype "passive"))
      (node (ref "U2") (pin "4") (pinfunction "PG_4") (pintype "bidirectional"))
    )
    (net (code "26") (name "Net-(U2-SS{slash}TR)") (class "Default")
      (node (ref "C31") (pin "2") (pinfunction "2_2") (pintype "bidirectional"))
      (node (ref "U2") (pin "9") (pinfunction "SS/TR_9") (pintype "bidirectional"))
    )
    (net (code "27") (name "Net-(U3-FB)") (class "Default")
      (node (ref "R52") (pin "2") (pinfunction "2_2") (pintype "passive"))
      (node (ref "R61") (pin "1") (pinfunction "1_1") (pintype "passive"))
      (node (ref "U3") (pin "5") (pinfunction "FB_5") (pintype "bidirectional"))
    )
    (net (code "28") (name "Net-(U3-PG)") (class "Default")
      (node (ref "R48") (pin "1") (pinfunction "1_1") (pintype "passive"))
      (node (ref "U3") (pin "4") (pinfunction "PG_4") (pintype "bidirectional"))
    )
    (net (code "29") (name "Net-(U3-SS{slash}TR)") (class "Default")
      (node (ref "C32") (pin "2") (pinfunction "2_2") (pintype "bidirectional"))
      (node (ref "U3") (pin "9") (pinfunction "SS/TR_9") (pintype "bidirectional"))
    )
    (net (code "30") (name "Net-(U4-FB)") (class "Default")
      (node (ref "R56") (pin "2") (pinfunction "2_2") (pintype "passive"))
      (node (ref "R63") (pin "1") (pinfunction "1_1") (pintype "passive"))
      (node (ref "U4") (pin "5") (pinfunction "FB_5") (pintype "bidirectional"))
    )
    (net (code "31") (name "Net-(U4-PG)") (class "Default")
      (node (ref "R45") (pin "1") (pinfunction "1_1") (pintype "passive"))
      (node (ref "U4") (pin "4") (pinfunction "PG_4") (pintype "bidirectional"))
    )
    (net (code "32") (name "Net-(U4-SS{slash}TR)") (class "Default")
      (node (ref "C29") (pin "2") (pinfunction "2_2") (pintype "bidirectional"))
      (node (ref "U4") (pin "9") (pinfunction "SS/TR_9") (pintype "bidirectional"))
    )
    (net (code "33") (name "Net-(U5-FB)") (class "Default")
      (node (ref "R53") (pin "2") (pinfunction "2_2") (pintype "passive"))
      (node (ref "R62") (pin "1") (pinfunction "1_1") (pintype "passive"))
      (node (ref "U5") (pin "5") (pinfunction "FB_5") (pintype "bidirectional"))
    )
    (net (code "34") (name "Net-(U5-PG)") (class "Default")
      (node (ref "R49") (pin "1") (pinfunction "1_1") (pintype "passive"))
      (node (ref "U5") (pin "4") (pinfunction "PG_4") (pintype "bidirectional"))
    )
    (net (code "35") (name "Net-(U5-SS{slash}TR)") (class "Default")
      (node (ref "C33") (pin "2") (pinfunction "2_2") (pintype "bidirectional"))
      (node (ref "U5") (pin "9") (pinfunction "SS/TR_9") (pintype "bidirectional"))
    )
    (net (code "36") (name "Net-(U6-SC0)") (class "Default")
      (node (ref "R18") (pin "1") (pinfunction "1_1") (pintype "passive"))
      (node (ref "U6") (pin "6") (pinfunction "SC0_6") (pintype "bidirectional"))
      (node (ref "U8") (pin "3") (pinfunction "SCL_3") (pintype "open_collector"))
    )
    (net (code "37") (name "Net-(U6-SC1)") (class "Default")
      (node (ref "R21") (pin "1") (pinfunction "1_1") (pintype "passive"))
      (node (ref "U6") (pin "9") (pinfunction "SC1_9") (pintype "bidirectional"))
      (node (ref "U9") (pin "P4") (pinfunction "SCL_P4") (pintype "open_collector"))
    )
    (net (code "38") (name "Net-(U6-SD0)") (class "Default")
      (node (ref "R17") (pin "1") (pinfunction "1_1") (pintype "passive"))
      (node (ref "U6") (pin "5") (pinfunction "SD0_5") (pintype "bidirectional"))
      (node (ref "U8") (pin "4") (pinfunction "SDA_4") (pintype "open_collector"))
    )
    (net (code "39") (name "Net-(U6-SD1)") (class "Default")
      (node (ref "R20") (pin "1") (pinfunction "1_1") (pintype "passive"))
      (node (ref "U6") (pin "8") (pinfunction "SD1_8") (pintype "bidirectional"))
      (node (ref "U9") (pin "P5") (pinfunction "SDA_P5") (pintype "open_collector"))
    )
    (net (code "40") (name "Net-(U6-~{INT0})") (class "Default")
      (node (ref "R19") (pin "1") (pinfunction "1_1") (pintype "passive"))
      (node (ref "U6") (pin "4") (pinfunction "~{INT0}_4") (pintype "bidirectional"))
      (node (ref "U8") (pin "5") (pinfunction "~{ALERT}_5") (pintype "open_collector"))
    )
    (net (code "41") (name "Net-(U6-~{INT1})") (class "Default")
      (node (ref "R22") (pin "1") (pinfunction "1_1") (pintype "passive"))
      (node (ref "U6") (pin "7") (pinfunction "~{INT1}_7") (pintype "bidirectional"))
      (node (ref "U9") (pin "P6") (pinfunction "~{ALERT}_P6") (pintype "open_collector"))
    )
    (net (code "42") (name "Net-(U10-SCL)") (class "Default")
      (node (ref "R24") (pin "1") (pinfunction "1_1") (pintype "passive"))
      (node (ref "U10") (pin "P4") (pinfunction "SCL_P4") (pintype "open_collector"))
      (node (ref "U6") (pin "13") (pinfunction "SC2_13") (pintype "bidirectional"))
    )
    (net (code "43") (name "Net-(U10-SDA)") (class "Default")
      (node (ref "R23") (pin "1") (pinfunction "1_1") (pintype "passive"))
      (node (ref "U10") (pin "P5") (pinfunction "SDA_P5") (pintype "open_collector"))
      (node (ref "U6") (pin "12") (pinfunction "SD2_12") (pintype "bidirectional"))
    )
    (net (code "44") (name "Net-(U10-~{ALERT})") (class "Default")
      (node (ref "R25") (pin "1") (pinfunction "1_1") (pintype "passive"))
      (node (ref "U10") (pin "P6") (pinfunction "~{ALERT}_P6") (pintype "open_collector"))
      (node (ref "U6") (pin "11") (pinfunction "~{INT2}_11") (pintype "bidirectional"))
    )
    (net (code "45") (name "Net-(U11-SCL)") (class "Default")
      (node (ref "R27") (pin "1") (pinfunction "1_1") (pintype "passive"))
      (node (ref "U11") (pin "P4") (pinfunction "SCL_P4") (pintype "open_collector"))
      (node (ref "U6") (pin "16") (pinfunction "SC3_16") (pintype "bidirectional"))
    )
    (net (code "46") (name "Net-(U11-SDA)") (class "Default")
      (node (ref "R26") (pin "1") (pinfunction "1_1") (pintype "passive"))
      (node (ref "U11") (pin "P5") (pinfunction "SDA_P5") (pintype "open_collector"))
      (node (ref "U6") (pin "15") (pinfunction "SD3_15") (pintype "bidirectional"))
    )
    (net (code "47") (name "Net-(U11-~{ALERT})") (class "Default")
      (node (ref "R28") (pin "1") (pinfunction "1_1") (pintype "passive"))
      (node (ref "U11") (pin "P6") (pinfunction "~{ALERT}_P6") (pintype "open_collector"))
      (node (ref "U6") (pin "14") (pinfunction "~{INT3}_14") (pintype "bidirectional"))
    )
    (net (code "48") (name "Net-(U12-SCL)") (class "Default")
      (node (ref "R36") (pin "1") (pinfunction "1_1") (pintype "passive"))
      (node (ref "U12") (pin "P4") (pinfunction "SCL_P4") (pintype "open_collector"))
      (node (ref "U7") (pin "6") (pinfunction "SC0_6") (pintype "bidirectional"))
    )
    (net (code "49") (name "Net-(U12-SDA)") (class "Default")
      (node (ref "R35") (pin "1") (pinfunction "1_1") (pintype "passive"))
      (node (ref "U12") (pin "P5") (pinfunction "SDA_P5") (pintype "open_collector"))
      (node (ref "U7") (pin "5") (pinfunction "SD0_5") (pintype "bidirectional"))
    )
    (net (code "50") (name "Net-(U12-~{ALERT})") (class "Default")
      (node (ref "R37") (pin "1") (pinfunction "1_1") (pintype "passive"))
      (node (ref "U12") (pin "P6") (pinfunction "~{ALERT}_P6") (pintype "open_collector"))
      (node (ref "U7") (pin "4") (pinfunction "~{INT0}_4") (pintype "bidirectional"))
    )
    (net (code "51") (name "Net-(U13-SCL)") (class "Default")
      (node (ref "R33") (pin "1") (pinfunction "1_1") (pintype "passive"))
      (node (ref "U13") (pin "P4") (pinfunction "SCL_P4") (pintype "open_collector"))
      (node (ref "U7") (pin "9") (pinfunction "SC1_9") (pintype "bidirectional"))
    )
    (net (code "52") (name "Net-(U13-SDA)") (class "Default")
      (node (ref "R32") (pin "1") (pinfunction "1_1") (pintype "passive"))
      (node (ref "U13") (pin "P5") (pinfunction "SDA_P5") (pintype "open_collector"))
      (node (ref "U7") (pin "8") (pinfunction "SD1_8") (pintype "bidirectional"))
    )
    (net (code "53") (name "Net-(U13-~{ALERT})") (class "Default")
      (node (ref "R34") (pin "1") (pinfunction "1_1") (pintype "passive"))
      (node (ref "U13") (pin "P6") (pinfunction "~{ALERT}_P6") (pintype "open_collector"))
      (node (ref "U7") (pin "7") (pinfunction "~{INT1}_7") (pintype "bidirectional"))
    )
    (net (code "54") (name "Net-(U14-SCL)") (class "Default")
      (node (ref "R30") (pin "1") (pinfunction "1_1") (pintype "passive"))
      (node (ref "U14") (pin "P4") (pinfunction "SCL_P4") (pintype "open_collector"))
      (node (ref "U7") (pin "13") (pinfunction "SC2_13") (pintype "bidirectional"))
    )
    (net (code "55") (name "Net-(U14-SDA)") (class "Default")
      (node (ref "R29") (pin "1") (pinfunction "1_1") (pintype "passive"))
      (node (ref "U14") (pin "P5") (pinfunction "SDA_P5") (pintype "open_collector"))
      (node (ref "U7") (pin "12") (pinfunction "SD2_12") (pintype "bidirectional"))
    )
    (net (code "56") (name "Net-(U14-~{ALERT})") (class "Default")
      (node (ref "R31") (pin "1") (pinfunction "1_1") (pintype "passive"))
      (node (ref "U14") (pin "P6") (pinfunction "~{ALERT}_P6") (pintype "open_collector"))
      (node (ref "U7") (pin "11") (pinfunction "~{INT2}_11") (pintype "bidirectional"))
    )
    (net (code "57") (name "Net-(U15-SCL)") (class "Default")
      (node (ref "R39") (pin "1") (pinfunction "1_1") (pintype "passive"))
      (node (ref "U15") (pin "P4") (pinfunction "SCL_P4") (pintype "open_collector"))
      (node (ref "U7") (pin "16") (pinfunction "SC3_16") (pintype "bidirectional"))
    )
    (net (code "58") (name "Net-(U15-SDA)") (class "Default")
      (node (ref "R38") (pin "1") (pinfunction "1_1") (pintype "passive"))
      (node (ref "U15") (pin "P5") (pinfunction "SDA_P5") (pintype "open_collector"))
      (node (ref "U7") (pin "15") (pinfunction "SD3_15") (pintype "bidirectional"))
    )
    (net (code "59") (name "Net-(U15-~{ALERT})") (class "Default")
      (node (ref "R40") (pin "1") (pinfunction "1_1") (pintype "passive"))
      (node (ref "U15") (pin "P6") (pinfunction "~{ALERT}_P6") (pintype "open_collector"))
      (node (ref "U7") (pin "14") (pinfunction "~{INT3}_14") (pintype "bidirectional"))
    )
    (net (code "60") (name "Net-(U16-VFB)") (class "Default")
      (node (ref "R58") (pin "1") (pinfunction "1_1") (pintype "passive"))
      (node (ref "R64") (pin "1") (pinfunction "1_1") (pintype "passive"))
      (node (ref "U16") (pin "7") (pinfunction "VFB_7") (pintype "bidirectional"))
    )
    (net (code "61") (name "Net-(U16-VIN_REG)") (class "Default")
      (node (ref "R12") (pin "1") (pinfunction "1_1") (pintype "passive"))
      (node (ref "R44") (pin "2") (pinfunction "2_2") (pintype "passive"))
      (node (ref "R57") (pin "1") (pinfunction "1_1") (pintype "passive"))
      (node (ref "U16") (pin "2") (pinfunction "VIN_REG_2") (pintype "bidirectional"))
      (node (ref "U17") (pin "6") (pinfunction "V-_6") (pintype "bidirectional"))
    )
    (net (code "62") (name "Net-(U17-R)") (class "Default")
      (node (ref "R12") (pin "2") (pinfunction "2_2") (pintype "passive"))
      (node (ref "U17") (pin "1") (pinfunction "R_1") (pintype "bidirectional"))
    )
    (net (code "63") (name "Net-(U18-ALRT1)") (class "Default")
      (node (ref "R13") (pin "1") (pinfunction "1_1") (pintype "passive"))
      (node (ref "U18") (pin "8") (pinfunction "ALRT1_8") (pintype "bidirectional"))
      (node (ref "U19") (pin "P$6") (pinfunction "VUSB_P$6") (pintype "bidirectional"))
    )
    (net (code "64") (name "Net-(U18-REG2)") (class "Default")
      (node (ref "C24") (pin "1") (pinfunction "1_1") (pintype "bidirectional"))
      (node (ref "U18") (pin "3") (pinfunction "REG2_3") (pintype "bidirectional"))
    )
    (net (code "65") (name "Net-(U18-REG3)") (class "Default")
      (node (ref "C25") (pin "1") (pinfunction "1_1") (pintype "bidirectional"))
      (node (ref "U18") (pin "1") (pinfunction "REG3_1") (pintype "bidirectional"))
    )
    (net (code "66") (name "Net-(U18-SCL)") (class "Default")
      (node (ref "R55") (pin "1") (pinfunction "1_1") (pintype "passive"))
      (node (ref "U18") (pin "11") (pinfunction "SCL_11") (pintype "bidirectional"))
      (node (ref "U19") (pin "P$5") (pinfunction "D+_P$5") (pintype "bidirectional"))
    )
    (net (code "67") (name "Net-(U18-SDA)") (class "Default")
      (node (ref "R54") (pin "1") (pinfunction "1_1") (pintype "passive"))
      (node (ref "U18") (pin "12") (pinfunction "SDA_12") (pintype "bidirectional"))
      (node (ref "U19") (pin "P$4") (pinfunction "D-_P$4") (pintype "bidirectional"))
    )
    (net (code "68") (name "Net-(U25-SC0)") (class "Default")
      (node (ref "R42") (pin "1") (pinfunction "1_1") (pintype "passive"))
      (node (ref "U25") (pin "6") (pinfunction "SC0_6") (pintype "bidirectional"))
      (node (ref "U26") (pin "P4") (pinfunction "SCL_P4") (pintype "open_collector"))
    )
    (net (code "69") (name "Net-(U25-SD0)") (class "Default")
      (node (ref "R41") (pin "1") (pinfunction "1_1") (pintype "passive"))
      (node (ref "U25") (pin "5") (pinfunction "SD0_5") (pintype "bidirectional"))
      (node (ref "U26") (pin "P5") (pinfunction "SDA_P5") (pintype "open_collector"))
    )
    (net (code "70") (name "Net-(U25-~{INT0})") (class "Default")
      (node (ref "R43") (pin "1") (pinfunction "1_1") (pintype "passive"))
      (node (ref "U25") (pin "4") (pinfunction "~{INT0}_4") (pintype "bidirectional"))
      (node (ref "U26") (pin "P6") (pinfunction "~{ALERT}_P6") (pintype "open_collector"))
    )
    (net (code "71") (name "Net-(U27-SRT)") (class "Default")
      (node (ref "C27") (pin "1") (pinfunction "1_1") (pintype "bidirectional"))
      (node (ref "U27") (pin "3") (pinfunction "SRT_3") (pintype "bidirectional"))
    )
    (net (code "72") (name "Net-(U27-SWT)") (class "Default")
      (node (ref "S1") (pin "IN") (pinfunction "IN_IN") (pintype "bidirectional"))
      (node (ref "U27") (pin "2") (pinfunction "SWT_2") (pintype "bidirectional"))
    )
    (net (code "73") (name "Net-(U27-VCC)") (class "Default")
      (node (ref "C22") (pin "1") (pinfunction "1_1") (pintype "bidirectional"))
      (node (ref "U27") (pin "5") (pinfunction "WDS_5") (pintype "bidirectional"))
      (node (ref "U27") (pin "8") (pinfunction "VCC_8") (pintype "bidirectional"))
      (node (ref "U28") (pin "1") (pinfunction "OUT_1") (pintype "bidirectional"))
      (node (ref "U30") (pin "5") (pinfunction "VCC_5") (pintype "bidirectional"))
    )
    (net (code "74") (name "Net-(U27-~{MR})") (class "Default")
      (node (ref "S2") (pin "1") (pinfunction "P$1_1") (pintype "passive"))
      (node (ref "S2") (pin "2") (pinfunction "P$1_2") (pintype "passive"))
      (node (ref "U27") (pin "1") (pinfunction "~{MR}_1") (pintype "bidirectional"))
    )
    (net (code "75") (name "Net-(U29-~{WC})") (class "Default")
      (node (ref "SJ1") (pin "2") (pinfunction "2_2") (pintype "passive"))
      (node (ref "U29") (pin "7") (pinfunction "~{WC}_7") (pintype "bidirectional"))
    )
    (net (code "76") (name "Net-(U30-Y)") (class "Default")
      (node (ref "R70") (pin "1") (pinfunction "1_1") (pintype "passive"))
      (node (ref "U30") (pin "4") (pinfunction "Y_4") (pintype "bidirectional"))
    )
    (net (code "77") (name "SCL") (class "Default")
      (node (ref "J1") (pin "5") (pinfunction "SMBCLK_5") (pintype "open_collector"))
      (node (ref "J3") (pin "1") (pinfunction "SCL_1") (pintype "bidirectional"))
      (node (ref "R55") (pin "2") (pinfunction "2_2") (pintype "passive"))
      (node (ref "U25") (pin "18") (pinfunction "SCL_18") (pintype "bidirectional"))
      (node (ref "U29") (pin "6") (pinfunction "SCL_6") (pintype "bidirectional"))
      (node (ref "U6") (pin "18") (pinfunction "SCL_18") (pintype "bidirectional"))
      (node (ref "U7") (pin "18") (pinfunction "SCL_18") (pintype "bidirectional"))
    )
    (net (code "78") (name "SDA") (class "Default")
      (node (ref "J1") (pin "3") (pinfunction "SMBDATA_3") (pintype "open_collector"))
      (node (ref "J3") (pin "5") (pinfunction "SDA_5") (pintype "bidirectional"))
      (node (ref "R54") (pin "2") (pinfunction "2_2") (pintype "passive"))
      (node (ref "U25") (pin "19") (pinfunction "SDA_19") (pintype "bidirectional"))
      (node (ref "U29") (pin "5") (pinfunction "SDA_5") (pintype "bidirectional"))
      (node (ref "U6") (pin "19") (pinfunction "SDA_19") (pintype "bidirectional"))
      (node (ref "U7") (pin "19") (pinfunction "SDA_19") (pintype "bidirectional"))
    )
    (net (code "79") (name "VBAT+") (class "Default")
      (node (ref "C10") (pin "1") (pinfunction "1_1") (pintype "bidirectional"))
      (node (ref "C11") (pin "1") (pinfunction "1_1") (pintype "bidirectional"))
      (node (ref "C12") (pin "1") (pinfunction "1_1") (pintype "bidirectional"))
      (node (ref "C13") (pin "1") (pinfunction "1_1") (pintype "bidirectional"))
      (node (ref "C14") (pin "1") (pinfunction "1_1") (pintype "bidirectional"))
      (node (ref "C21") (pin "1") (pinfunction "1_1") (pintype "bidirectional"))
      (node (ref "C34") (pin "P$1") (pinfunction "1_P$1") (pintype "bidirectional"))
      (node (ref "C35") (pin "P$1") (pinfunction "1_P$1") (pintype "bidirectional"))
      (node (ref "C36") (pin "P$1") (pinfunction "1_P$1") (pintype "bidirectional"))
      (node (ref "C37") (pin "P$1") (pinfunction "1_P$1") (pintype "bidirectional"))
      (node (ref "C38") (pin "P$1") (pinfunction "1_P$1") (pintype "bidirectional"))
      (node (ref "C39") (pin "P$1") (pinfunction "1_P$1") (pintype "bidirectional"))
      (node (ref "C9") (pin "1") (pinfunction "1_1") (pintype "bidirectional"))
      (node (ref "D2") (pin "P$1") (pinfunction "CATHODE_P$1") (pintype "bidirectional"))
      (node (ref "J1") (pin "17") (pinfunction "VBATT+_17") (pintype "power_in"))
      (node (ref "JP1") (pin "4") (pinfunction "4_4") (pintype "passive"))
      (node (ref "R10") (pin "2") (pinfunction "2_2") (pintype "passive"))
      (node (ref "R64") (pin "2") (pinfunction "2_2") (pintype "passive"))
      (node (ref "U1") (pin "10") (pinfunction "AVIN_10") (pintype "bidirectional"))
      (node (ref "U1") (pin "11") (pinfunction "PVIN_11") (pintype "bidirectional"))
      (node (ref "U1") (pin "12") (pinfunction "PVIN_12") (pintype "bidirectional"))
      (node (ref "U16") (pin "9") (pinfunction "BAT_9") (pintype "bidirectional"))
      (node (ref "U18") (pin "5") (pinfunction "VBATT_5") (pintype "bidirectional"))
      (node (ref "U2") (pin "10") (pinfunction "AVIN_10") (pintype "bidirectional"))
      (node (ref "U2") (pin "11") (pinfunction "PVIN_11") (pintype "bidirectional"))
      (node (ref "U2") (pin "12") (pinfunction "PVIN_12") (pintype "bidirectional"))
      (node (ref "U28") (pin "2") (pinfunction "IN_2") (pintype "bidirectional"))
      (node (ref "U3") (pin "10") (pinfunction "AVIN_10") (pintype "bidirectional"))
      (node (ref "U3") (pin "11") (pinfunction "PVIN_11") (pintype "bidirectional"))
      (node (ref "U3") (pin "12") (pinfunction "PVIN_12") (pintype "bidirectional"))
      (node (ref "U4") (pin "10") (pinfunction "AVIN_10") (pintype "bidirectional"))
      (node (ref "U4") (pin "11") (pinfunction "PVIN_11") (pintype "bidirectional"))
      (node (ref "U4") (pin "12") (pinfunction "PVIN_12") (pintype "bidirectional"))
      (node (ref "U5") (pin "10") (pinfunction "AVIN_10") (pintype "bidirectional"))
      (node (ref "U5") (pin "11") (pinfunction "PVIN_11") (pintype "bidirectional"))
      (node (ref "U5") (pin "12") (pinfunction "PVIN_12") (pintype "bidirectional"))
    )
    (net (code "80") (name "VBAT-") (class "Default")
      (node (ref "J1") (pin "18") (pinfunction "VBATT-_18") (pintype "power_in"))
      (node (ref "JP1") (pin "3") (pinfunction "3_3") (pintype "passive"))
      (node (ref "R1") (pin "1") (pinfunction "1_1") (pintype "passive"))
      (node (ref "U18") (pin "2") (pinfunction "CSP_2") (pintype "bidirectional"))
    )
    (net (code "81") (name "VCC_3V3") (class "Default")
      (node (ref "C15") (pin "1") (pinfunction "1_1") (pintype "bidirectional"))
      (node (ref "C46") (pin "2") (pinfunction "2_2") (pintype "bidirectional"))
      (node (ref "R17") (pin "2") (pinfunction "2_2") (pintype "passive"))
      (node (ref "R18") (pin "2") (pinfunction "2_2") (pintype "passive"))
      (node (ref "R19") (pin "2") (pinfunction "2_2") (pintype "passive"))
      (node (ref "R2") (pin "2") (pinfunction "2_2") (pintype "passive"))
      (node (ref "TP1") (pin "TESTPOINT") (pinfunction "TESTPOINT_TESTPOINT") (pintype "bidirectional"))
      (node (ref "U20") (pin "5") (pinfunction "OUT_5") (pintype "bidirectional"))
      (node (ref "U8") (pin "1") (pinfunction "SENSE+_1") (pintype "open_collector"))
    )
    (net (code "82") (name "VCC_5V_1") (class "Default")
      (node (ref "C16") (pin "1") (pinfunction "1_1") (pintype "bidirectional"))
      (node (ref "C47") (pin "2") (pinfunction "2_2") (pintype "bidirectional"))
      (node (ref "R20") (pin "2") (pinfunction "2_2") (pintype "passive"))
      (node (ref "R21") (pin "2") (pinfunction "2_2") (pintype "passive"))
      (node (ref "R22") (pin "2") (pinfunction "2_2") (pintype "passive"))
      (node (ref "R3") (pin "2") (pinfunction "2_2") (pintype "passive"))
      (node (ref "TP2") (pin "TESTPOINT") (pinfunction "TESTPOINT_TESTPOINT") (pintype "bidirectional"))
      (node (ref "U21") (pin "5") (pinfunction "OUT_5") (pintype "bidirectional"))
      (node (ref "U9") (pin "P1") (pinfunction "SENSE+_P1") (pintype "open_collector"))
    )
    (net (code "83") (name "VCC_5V_2") (class "Default")
      (node (ref "C17") (pin "1") (pinfunction "1_1") (pintype "bidirectional"))
      (node (ref "C48") (pin "2") (pinfunction "2_2") (pintype "bidirectional"))
      (node (ref "R23") (pin "2") (pinfunction "2_2") (pintype "passive"))
      (node (ref "R24") (pin "2") (pinfunction "2_2") (pintype "passive"))
      (node (ref "R25") (pin "2") (pinfunction "2_2") (pintype "passive"))
      (node (ref "R26") (pin "2") (pinfunction "2_2") (pintype "passive"))
      (node (ref "R27") (pin "2") (pinfunction "2_2") (pintype "passive"))
      (node (ref "R28") (pin "2") (pinfunction "2_2") (pintype "passive"))
      (node (ref "R4") (pin "2") (pinfunction "2_2") (pintype "passive"))
      (node (ref "R5") (pin "2") (pinfunction "2_2") (pintype "passive"))
      (node (ref "TP3") (pin "TESTPOINT") (pinfunction "TESTPOINT_TESTPOINT") (pintype "bidirectional"))
      (node (ref "U10") (pin "P1") (pinfunction "SENSE+_P1") (pintype "open_collector"))
      (node (ref "U11") (pin "P1") (pinfunction "SENSE+_P1") (pintype "open_collector"))
      (node (ref "U22") (pin "5") (pinfunction "OUT_5") (pintype "bidirectional"))
    )
    (net (code "84") (name "VCC_5V_3") (class "Default")
      (node (ref "C18") (pin "1") (pinfunction "1_1") (pintype "bidirectional"))
      (node (ref "C49") (pin "2") (pinfunction "2_2") (pintype "bidirectional"))
      (node (ref "R32") (pin "2") (pinfunction "2_2") (pintype "passive"))
      (node (ref "R33") (pin "2") (pinfunction "2_2") (pintype "passive"))
      (node (ref "R34") (pin "2") (pinfunction "2_2") (pintype "passive"))
      (node (ref "R35") (pin "2") (pinfunction "2_2") (pintype "passive"))
      (node (ref "R36") (pin "2") (pinfunction "2_2") (pintype "passive"))
      (node (ref "R37") (pin "2") (pinfunction "2_2") (pintype "passive"))
      (node (ref "R6") (pin "2") (pinfunction "2_2") (pintype "passive"))
      (node (ref "R7") (pin "2") (pinfunction "2_2") (pintype "passive"))
      (node (ref "TP4") (pin "TESTPOINT") (pinfunction "TESTPOINT_TESTPOINT") (pintype "bidirectional"))
      (node (ref "U12") (pin "P1") (pinfunction "SENSE+_P1") (pintype "open_collector"))
      (node (ref "U13") (pin "P1") (pinfunction "SENSE+_P1") (pintype "open_collector"))
      (node (ref "U23") (pin "5") (pinfunction "OUT_5") (pintype "bidirectional"))
    )
    (net (code "85") (name "VCC_5V_4") (class "Default")
      (node (ref "C19") (pin "1") (pinfunction "1_1") (pintype "bidirectional"))
      (node (ref "C50") (pin "2") (pinfunction "2_2") (pintype "bidirectional"))
      (node (ref "R29") (pin "2") (pinfunction "2_2") (pintype "passive"))
      (node (ref "R30") (pin "2") (pinfunction "2_2") (pintype "passive"))
      (node (ref "R31") (pin "2") (pinfunction "2_2") (pintype "passive"))
      (node (ref "R38") (pin "2") (pinfunction "2_2") (pintype "passive"))
      (node (ref "R39") (pin "2") (pinfunction "2_2") (pintype "passive"))
      (node (ref "R40") (pin "2") (pinfunction "2_2") (pintype "passive"))
      (node (ref "R8") (pin "2") (pinfunction "2_2") (pintype "passive"))
      (node (ref "R9") (pin "2") (pinfunction "2_2") (pintype "passive"))
      (node (ref "TP5") (pin "TESTPOINT") (pinfunction "TESTPOINT_TESTPOINT") (pintype "bidirectional"))
      (node (ref "U14") (pin "P1") (pinfunction "SENSE+_P1") (pintype "open_collector"))
      (node (ref "U15") (pin "P1") (pinfunction "SENSE+_P1") (pintype "open_collector"))
      (node (ref "U24") (pin "5") (pinfunction "OUT_5") (pintype "bidirectional"))
    )
    (net (code "86") (name "VCC_BACKPLANE") (class "Default")
      (node (ref "C1") (pin "1") (pinfunction "1_1") (pintype "bidirectional"))
      (node (ref "C23") (pin "1") (pinfunction "1_1") (pintype "bidirectional"))
      (node (ref "J1") (pin "13") (pinfunction "VCC_BACKPLANE_13") (pintype "power_in"))
      (node (ref "J1") (pin "2") (pinfunction "VCC_CONTROLLER_2") (pintype "power_in"))
      (node (ref "J3") (pin "6") (pinfunction "VCC_6") (pintype "bidirectional"))
      (node (ref "Q1") (pin "3") (pinfunction "D_3") (pintype "passive"))
      (node (ref "R15") (pin "2") (pinfunction "2_2") (pintype "passive"))
      (node (ref "R16") (pin "2") (pinfunction "2_2") (pintype "passive"))
      (node (ref "R2") (pin "1") (pinfunction "1_1") (pintype "passive"))
      (node (ref "R41") (pin "2") (pinfunction "2_2") (pintype "passive"))
      (node (ref "R42") (pin "2") (pinfunction "2_2") (pintype "passive"))
      (node (ref "R43") (pin "2") (pinfunction "2_2") (pintype "passive"))
      (node (ref "SJ1") (pin "1") (pinfunction "1_1") (pintype "passive"))
      (node (ref "U25") (pin "2") (pinfunction "A1_2") (pintype "bidirectional"))
      (node (ref "U25") (pin "20") (pinfunction "VCC_20") (pintype "bidirectional"))
      (node (ref "U29") (pin "8") (pinfunction "VCC_8") (pintype "bidirectional"))
      (node (ref "U6") (pin "20") (pinfunction "VCC_20") (pintype "bidirectional"))
      (node (ref "U7") (pin "1") (pinfunction "A0_1") (pintype "bidirectional"))
      (node (ref "U7") (pin "20") (pinfunction "VCC_20") (pintype "bidirectional"))
      (node (ref "U8") (pin "6") (pinfunction "SENSE-_6") (pintype "open_collector"))
    )
    (net (code "87") (name "VCC_LINUX") (class "Default")
      (node (ref "C2") (pin "1") (pinfunction "1_1") (pintype "bidirectional"))
      (node (ref "J1") (pin "4") (pinfunction "VCC_LINUX_4") (pintype "power_in"))
      (node (ref "R3") (pin "1") (pinfunction "1_1") (pintype "passive"))
      (node (ref "U9") (pin "P8") (pinfunction "SENSE-_P8") (pintype "open_collector"))
    )
    (net (code "88") (name "VCC_MOD0") (class "Default")
      (node (ref "C3") (pin "1") (pinfunction "1_1") (pintype "bidirectional"))
      (node (ref "J1") (pin "7") (pinfunction "VCC_MOD0_7") (pintype "power_in"))
      (node (ref "R4") (pin "1") (pinfunction "1_1") (pintype "passive"))
      (node (ref "U10") (pin "P8") (pinfunction "SENSE-_P8") (pintype "open_collector"))
    )
    (net (code "89") (name "VCC_MOD1") (class "Default")
      (node (ref "C4") (pin "1") (pinfunction "1_1") (pintype "bidirectional"))
      (node (ref "J1") (pin "8") (pinfunction "VCC_MOD1_8") (pintype "power_in"))
      (node (ref "R5") (pin "1") (pinfunction "1_1") (pintype "passive"))
      (node (ref "U11") (pin "P8") (pinfunction "SENSE-_P8") (pintype "open_collector"))
    )
    (net (code "90") (name "VCC_MOD2") (class "Default")
      (node (ref "C5") (pin "1") (pinfunction "1_1") (pintype "bidirectional"))
      (node (ref "J1") (pin "9") (pinfunction "VCC_MOD2_9") (pintype "power_in"))
      (node (ref "R6") (pin "1") (pinfunction "1_1") (pintype "passive"))
      (node (ref "U12") (pin "P8") (pinfunction "SENSE-_P8") (pintype "open_collector"))
    )
    (net (code "91") (name "VCC_MOD5") (class "Default")
      (node (ref "C6") (pin "1") (pinfunction "1_1") (pintype "bidirectional"))
      (node (ref "J1") (pin "10") (pinfunction "VCC_MOD5_10") (pintype "power_in"))
      (node (ref "R7") (pin "1") (pinfunction "1_1") (pintype "passive"))
      (node (ref "U13") (pin "P8") (pinfunction "SENSE-_P8") (pintype "open_collector"))
    )
    (net (code "92") (name "VCC_MOD6") (class "Default")
      (node (ref "C7") (pin "1") (pinfunction "1_1") (pintype "bidirectional"))
      (node (ref "J1") (pin "11") (pinfunction "VCC_MOD6_11") (pintype "power_in"))
      (node (ref "R8") (pin "1") (pinfunction "1_1") (pintype "passive"))
      (node (ref "U14") (pin "P8") (pinfunction "SENSE-_P8") (pintype "open_collector"))
    )
    (net (code "93") (name "VCC_MOD7") (class "Default")
      (node (ref "C8") (pin "1") (pinfunction "1_1") (pintype "bidirectional"))
      (node (ref "J1") (pin "12") (pinfunction "VCC_MOD7_12") (pintype "power_in"))
      (node (ref "R9") (pin "1") (pinfunction "1_1") (pintype "passive"))
      (node (ref "U15") (pin "P8") (pinfunction "SENSE-_P8") (pintype "open_collector"))
    )
    (net (code "94") (name "VSOL+") (class "Default")
      (node (ref "C20") (pin "1") (pinfunction "1_1") (pintype "bidirectional"))
      (node (ref "J1") (pin "19") (pinfunction "VSOL+_19") (pintype "power_in"))
      (node (ref "JP1") (pin "2") (pinfunction "2_2") (pintype "passive"))
      (node (ref "R11") (pin "2") (pinfunction "2_2") (pintype "passive"))
      (node (ref "U26") (pin "P1") (pinfunction "SENSE+_P1") (pintype "open_collector"))
    )
    (net (code "95") (name "VSOL_SENSE") (class "Default")
      (node (ref "C40") (pin "P$1") (pinfunction "1_P$1") (pintype "bidirectional"))
      (node (ref "R11") (pin "1") (pinfunction "1_1") (pintype "passive"))
      (node (ref "R57") (pin "2") (pinfunction "2_2") (pintype "passive"))
      (node (ref "U16") (pin "1") (pinfunction "VIN_1") (pintype "bidirectional"))
      (node (ref "U16") (pin "3") (pinfunction "~{SHDN}_3") (pintype "bidirectional"))
      (node (ref "U17") (pin "4") (pinfunction "V+_4") (pintype "bidirectional"))
      (node (ref "U26") (pin "P8") (pinfunction "SENSE-_P8") (pintype "open_collector"))
    )
    (net (code "96") (name "WDI") (class "Default")
      (node (ref "J1") (pin "16") (pinfunction "WDI_16") (pintype "power_in"))
      (node (ref "U27") (pin "6") (pinfunction "WDI_6") (pintype "bidirectional"))
    )
    (net (code "97") (name "unconnected-(U16-NTC-Pad8)") (class "Default")
      (node (ref "U16") (pin "8") (pinfunction "NTC_8") (pintype "bidirectional"))
    )
    (net (code "98") (name "unconnected-(U18-AIN1-Pad9)") (class "Default")
      (node (ref "U18") (pin "9") (pinfunction "AIN1_9") (pintype "bidirectional"))
    )
    (net (code "99") (name "unconnected-(U18-AIN2-Pad10)") (class "Default")
      (node (ref "U18") (pin "10") (pinfunction "AIN2_10") (pintype "bidirectional"))
    )
    (net (code "100") (name "unconnected-(U18-THRM-Pad14)") (class "Default")
      (node (ref "U18") (pin "14") (pinfunction "THRM_14") (pintype "bidirectional"))
    )
    (net (code "101") (name "unconnected-(U20-FLG-Pad4)") (class "Default")
      (node (ref "U20") (pin "4") (pinfunction "FLG_4") (pintype "bidirectional"))
    )
    (net (code "102") (name "unconnected-(U21-FLG-Pad4)") (class "Default")
      (node (ref "U21") (pin "4") (pinfunction "FLG_4") (pintype "bidirectional"))
    )
    (net (code "103") (name "unconnected-(U22-FLG-Pad4)") (class "Default")
      (node (ref "U22") (pin "4") (pinfunction "FLG_4") (pintype "bidirectional"))
    )
    (net (code "104") (name "unconnected-(U23-FLG-Pad4)") (class "Default")
      (node (ref "U23") (pin "4") (pinfunction "FLG_4") (pintype "bidirectional"))
    )
    (net (code "105") (name "unconnected-(U24-FLG-Pad4)") (class "Default")
      (node (ref "U24") (pin "4") (pinfunction "FLG_4") (pintype "bidirectional"))
    )
    (net (code "106") (name "unconnected-(U25-SC1-Pad9)") (class "Default")
      (node (ref "U25") (pin "9") (pinfunction "SC1_9") (pintype "bidirectional"))
    )
    (net (code "107") (name "unconnected-(U25-SC2-Pad13)") (class "Default")
      (node (ref "U25") (pin "13") (pinfunction "SC2_13") (pintype "bidirectional"))
    )
    (net (code "108") (name "unconnected-(U25-SC3-Pad16)") (class "Default")
      (node (ref "U25") (pin "16") (pinfunction "SC3_16") (pintype "bidirectional"))
    )
    (net (code "109") (name "unconnected-(U25-SD1-Pad8)") (class "Default")
      (node (ref "U25") (pin "8") (pinfunction "SD1_8") (pintype "bidirectional"))
    )
    (net (code "110") (name "unconnected-(U25-SD2-Pad12)") (class "Default")
      (node (ref "U25") (pin "12") (pinfunction "SD2_12") (pintype "bidirectional"))
    )
    (net (code "111") (name "unconnected-(U25-SD3-Pad15)") (class "Default")
      (node (ref "U25") (pin "15") (pinfunction "SD3_15") (pintype "bidirectional"))
    )
    (net (code "112") (name "unconnected-(U25-~{INT1}-Pad7)") (class "Default")
      (node (ref "U25") (pin "7") (pinfunction "~{INT1}_7") (pintype "bidirectional"))
    )
    (net (code "113") (name "unconnected-(U25-~{INT2}-Pad11)") (class "Default")
      (node (ref "U25") (pin "11") (pinfunction "~{INT2}_11") (pintype "bidirectional"))
    )
    (net (code "114") (name "unconnected-(U25-~{INT3}-Pad14)") (class "Default")
      (node (ref "U25") (pin "14") (pinfunction "~{INT3}_14") (pintype "bidirectional"))
    )
    (net (code "115") (name "~{INT}") (class "Default")
      (node (ref "J1") (pin "6") (pinfunction "~{SMBALERT}_6") (pintype "bidirectional"))
      (node (ref "R13") (pin "2") (pinfunction "2_2") (pintype "passive"))
      (node (ref "U25") (pin "17") (pinfunction "~{INT}_17") (pintype "bidirectional"))
      (node (ref "U6") (pin "17") (pinfunction "~{INT}_17") (pintype "bidirectional"))
      (node (ref "U7") (pin "17") (pinfunction "~{INT}_17") (pintype "bidirectional"))
    )
    (net (code "116") (name "~{RESET}") (class "Default")
      (node (ref "TP8") (pin "TESTPOINT") (pinfunction "TESTPOINT_TESTPOINT") (pintype "bidirectional"))
      (node (ref "U1") (pin "13") (pinfunction "EN_13") (pintype "bidirectional"))
      (node (ref "U2") (pin "13") (pinfunction "EN_13") (pintype "bidirectional"))
      (node (ref "U27") (pin "7") (pinfunction "~{RESET}_7") (pintype "bidirectional"))
      (node (ref "U3") (pin "13") (pinfunction "EN_13") (pintype "bidirectional"))
      (node (ref "U30") (pin "2") (pinfunction "A_2") (pintype "bidirectional"))
      (node (ref "U4") (pin "13") (pinfunction "EN_13") (pintype "bidirectional"))
      (node (ref "U5") (pin "13") (pinfunction "EN_13") (pintype "bidirectional"))
    )
  )
)
